# time-decoders.net
KiCad netlist of a schematic drawn in EAGLE
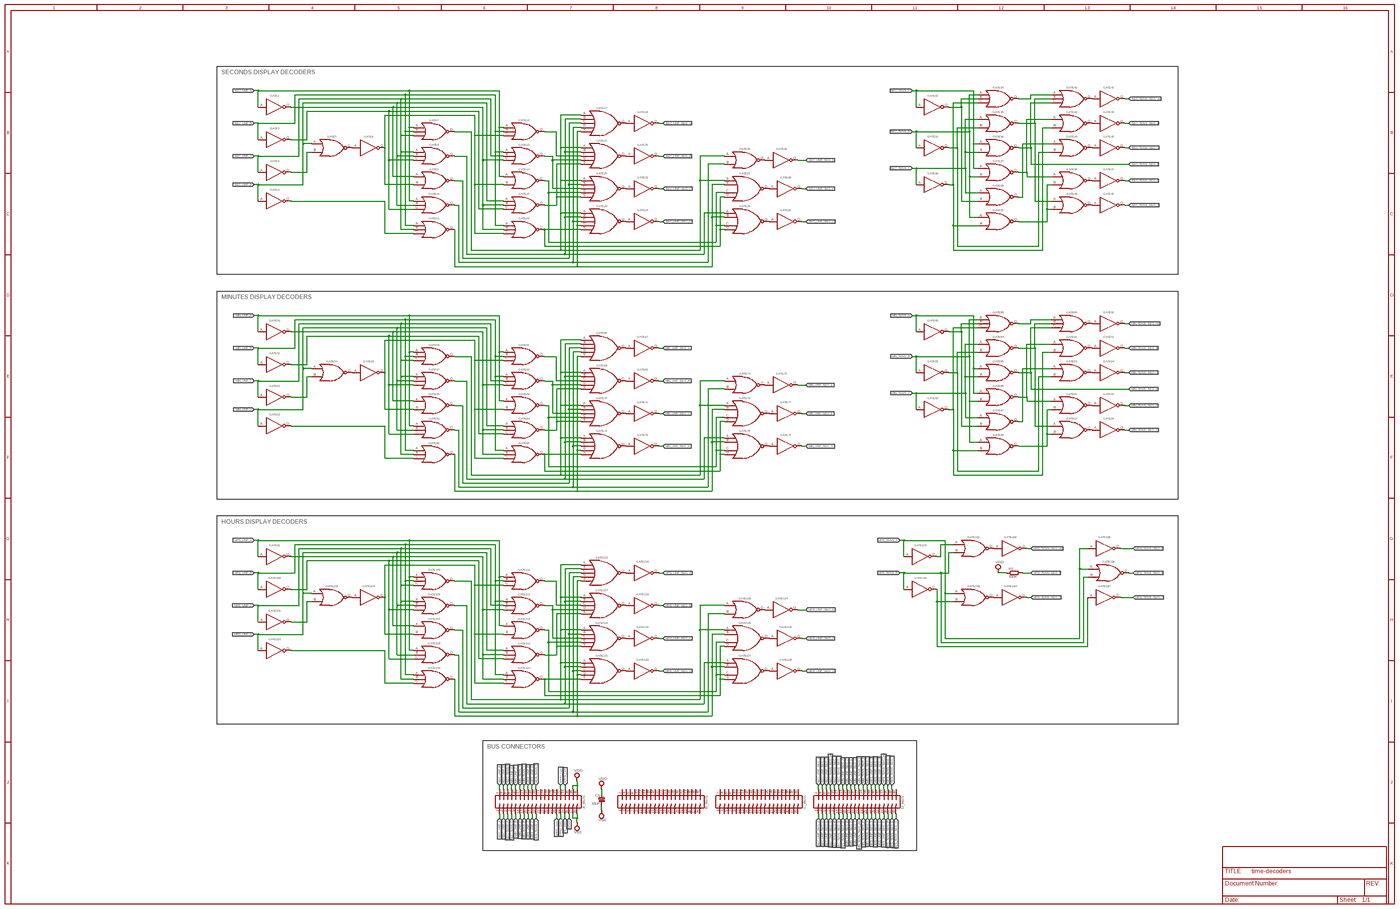
[diagram p0: schematic, sheet 1, overview]
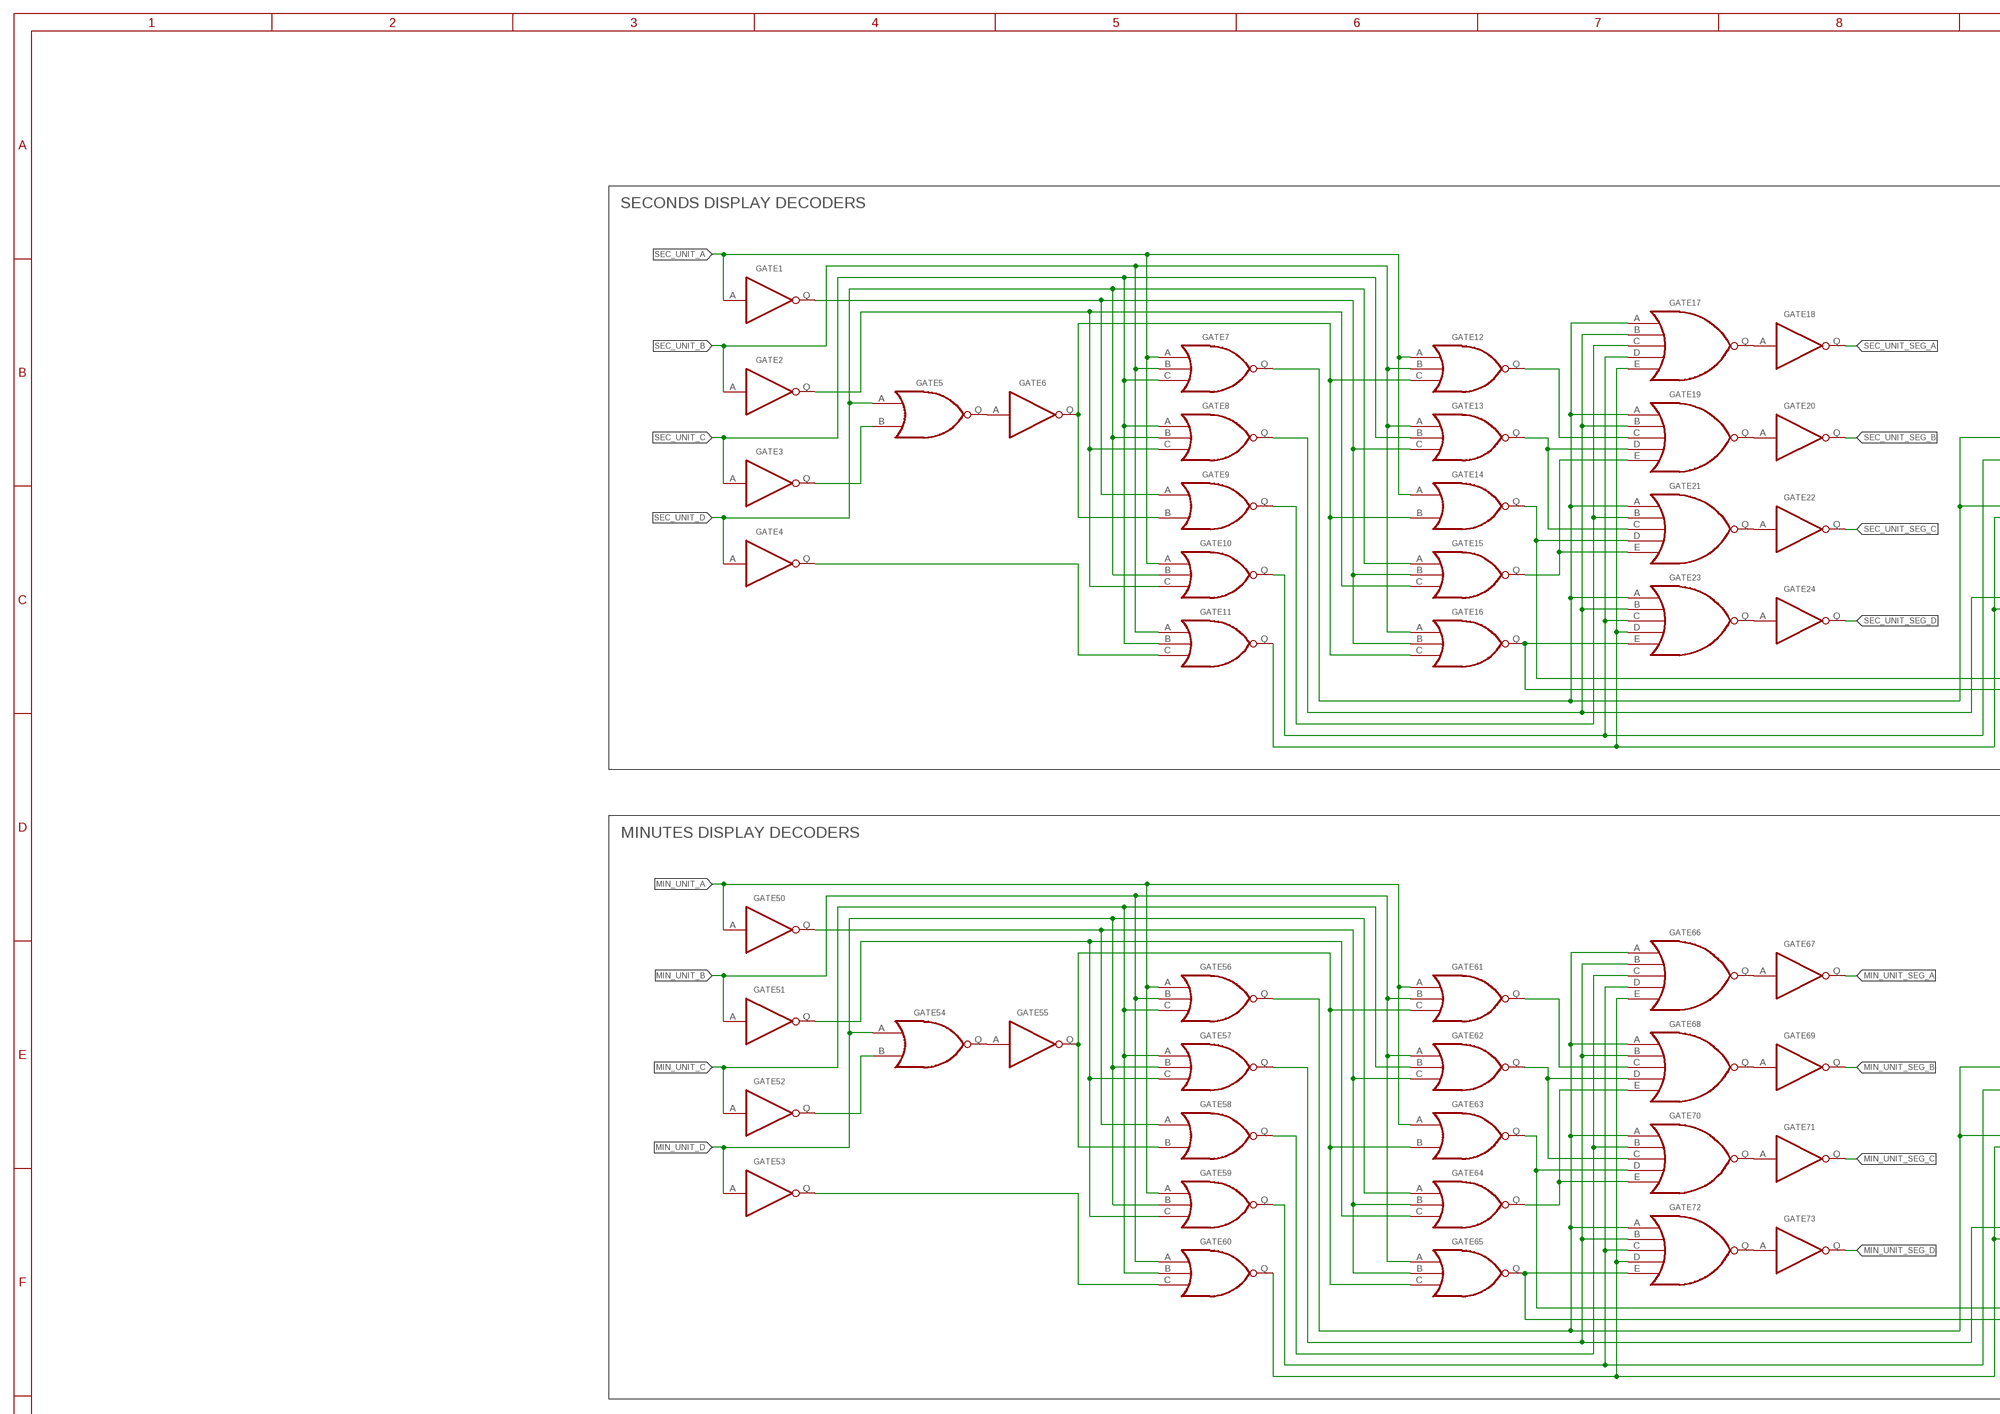
[diagram p1: schematic, sheet 1, part 1 of 4]
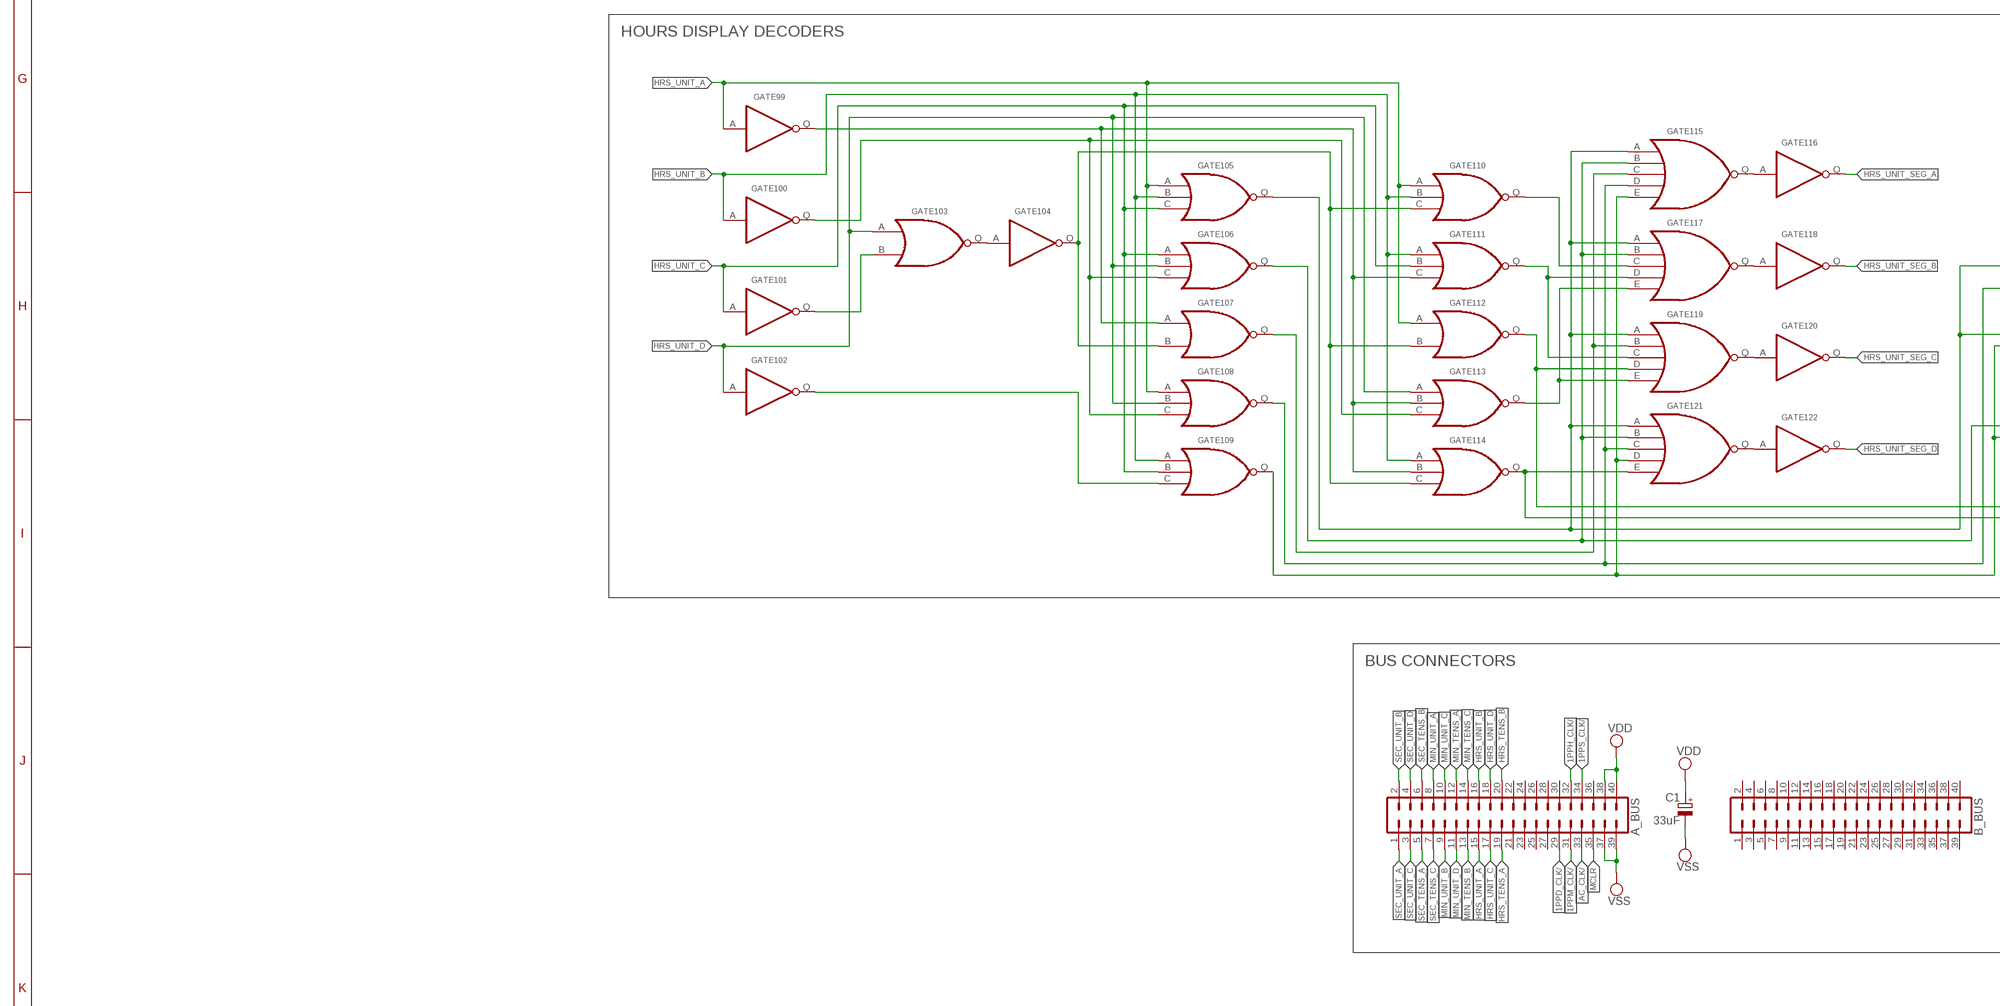
[diagram p2: schematic, sheet 1, part 2 of 4]
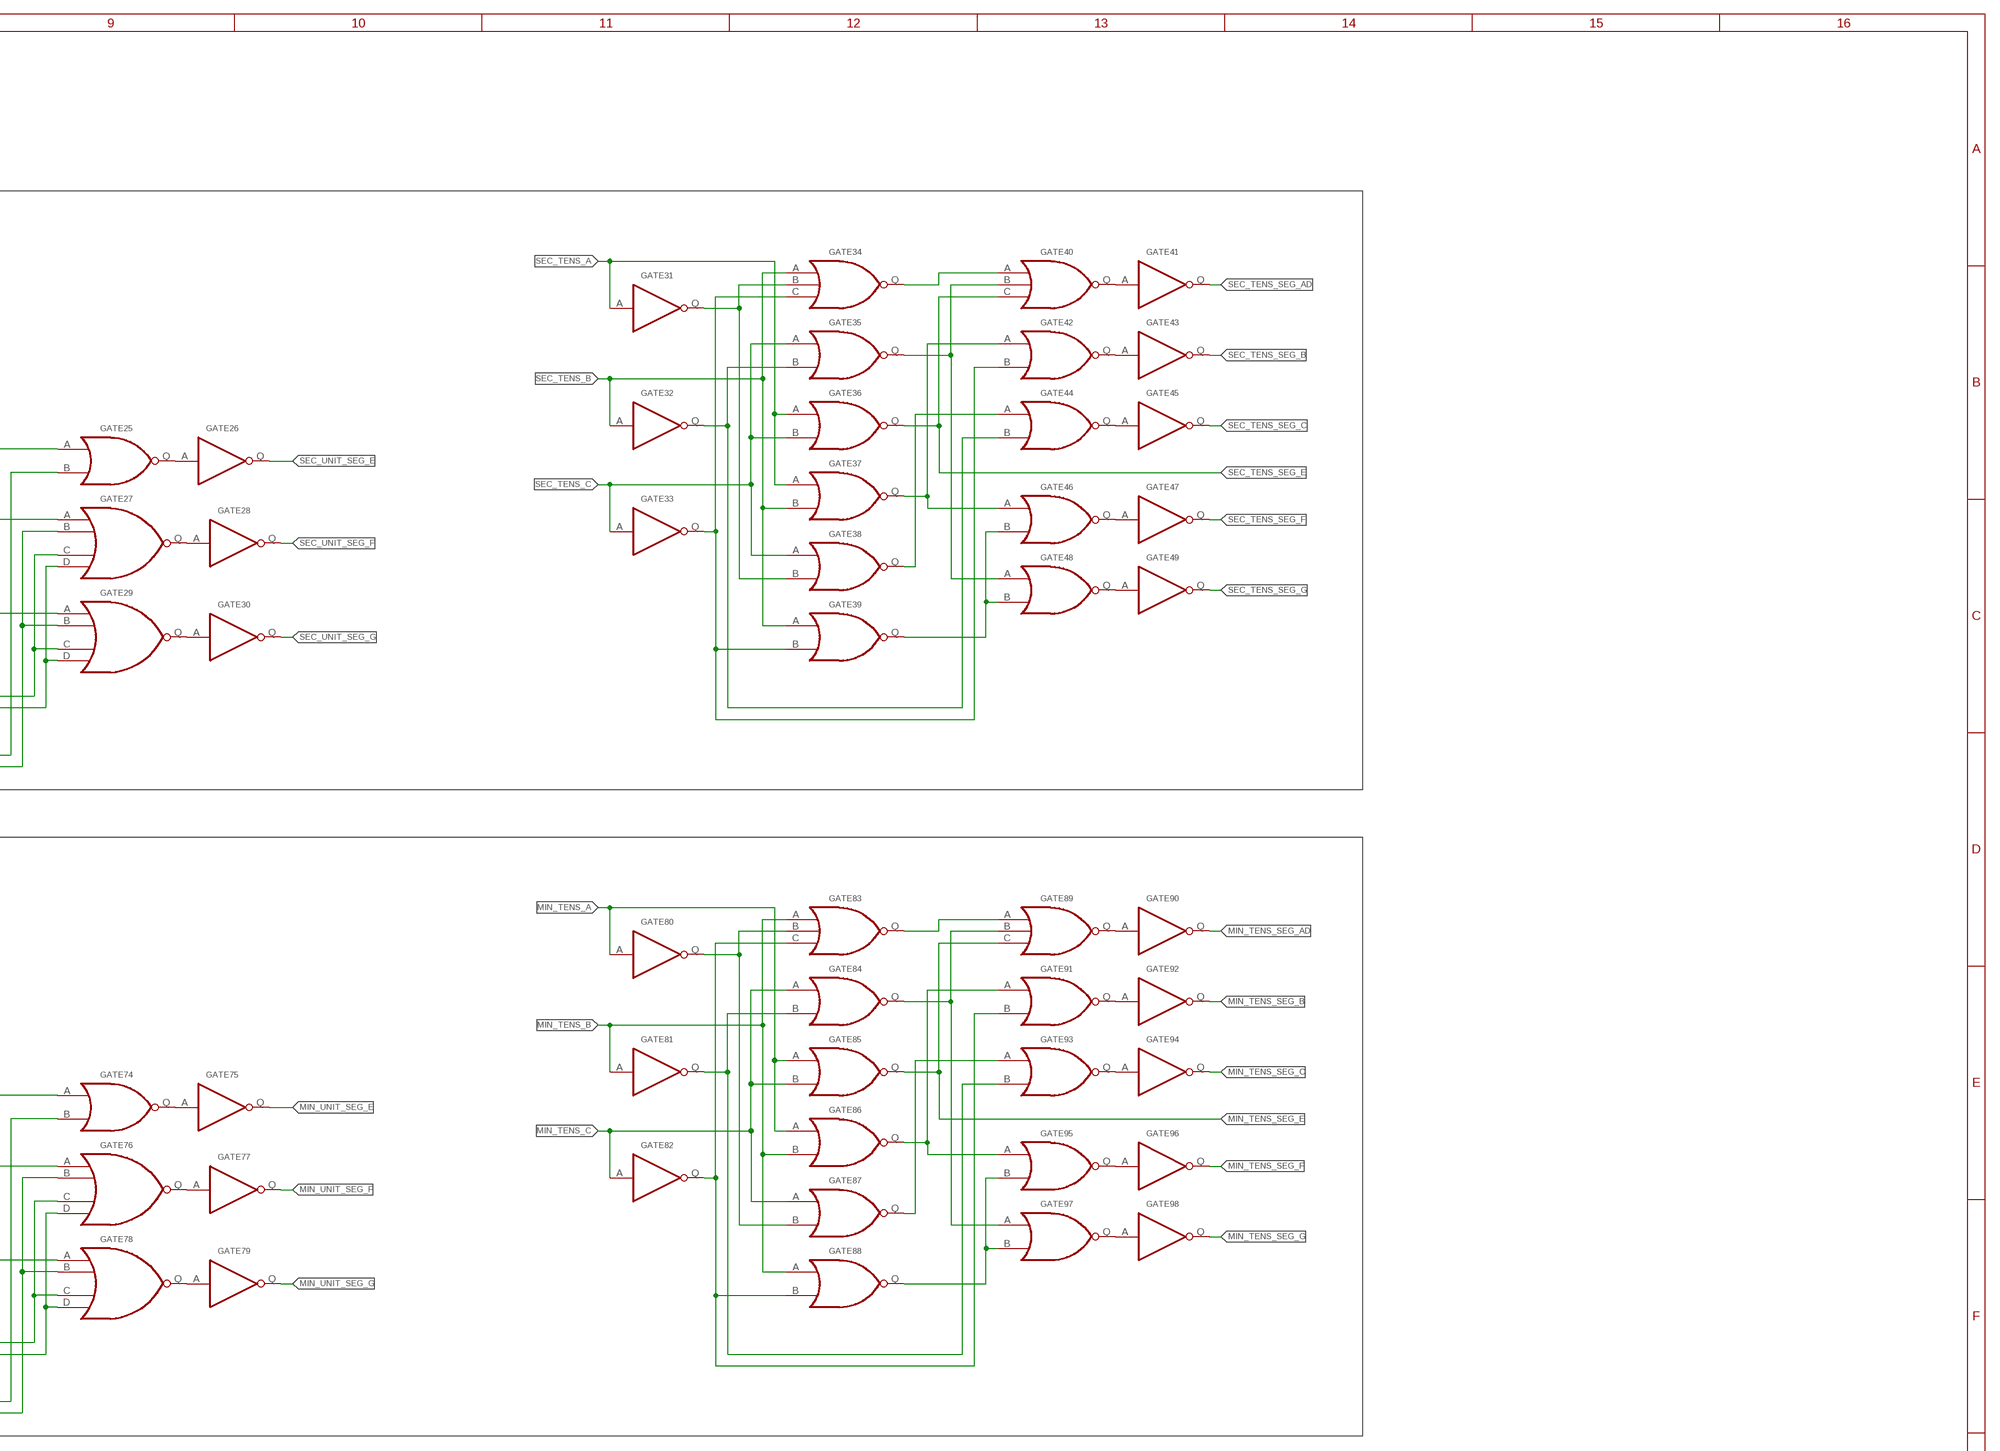
[diagram p3: schematic, sheet 1, part 3 of 4]
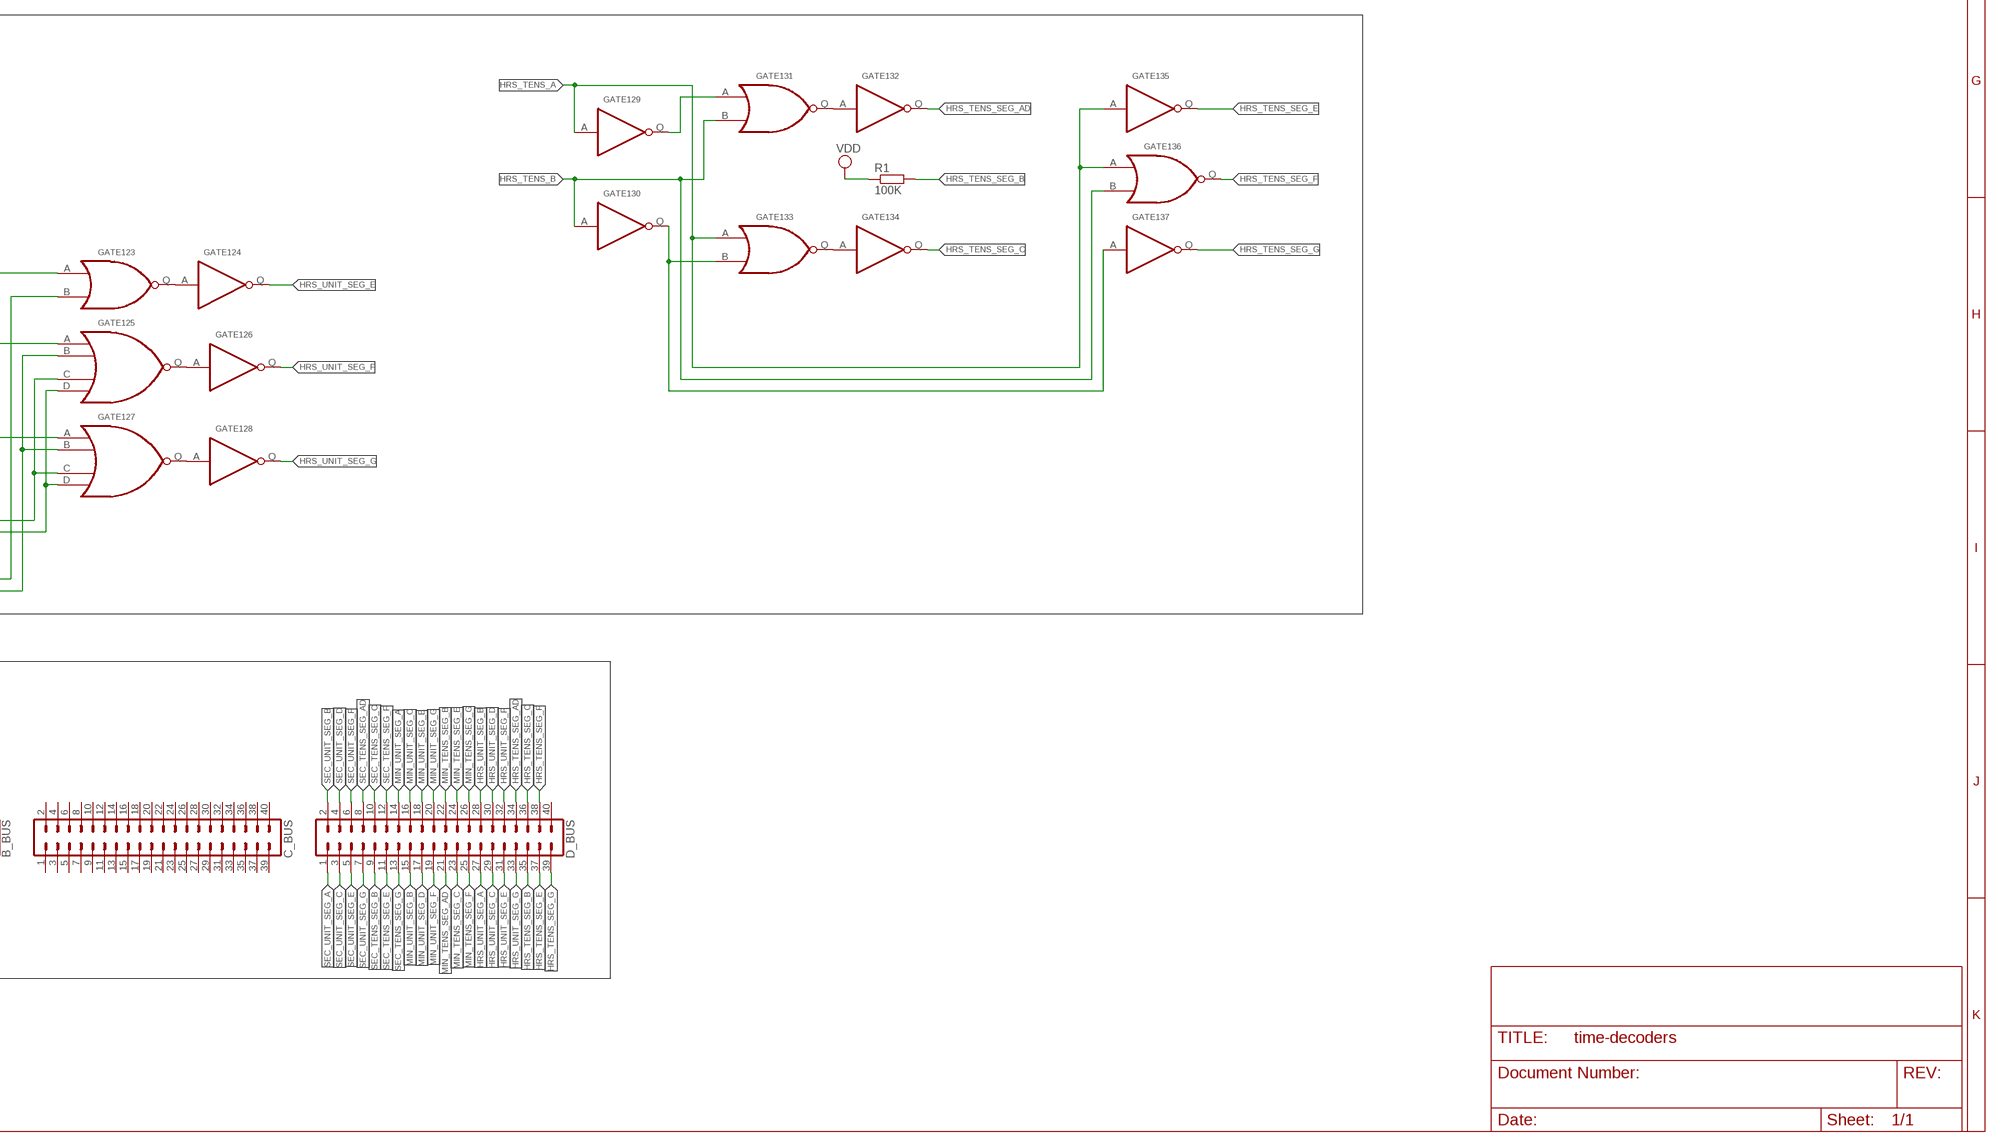
[diagram p4: schematic, sheet 1, part 4 of 4]

(export (version "E")
  (design (tool "Eeschema 10.0.6"))
  (components
    (comp (ref "A_BUS")
      (value "MA20-2")
      (footprint "eagle-import:MA20-2")
      (libsource (lib "eagle-import") (part "MA20-2"))
    )
    (comp (ref "B_BUS")
      (value "MA20-2")
      (footprint "eagle-import:MA20-2")
      (libsource (lib "eagle-import") (part "MA20-2"))
    )
    (comp (ref "C1")
      (value "33uF")
      (footprint "eagle-import:E2,5-6")
      (libsource (lib "eagle-import") (part "CPOL-EUE2.5-6"))
    )
    (comp (ref "C_BUS")
      (value "MA20-2")
      (footprint "eagle-import:MA20-2")
      (libsource (lib "eagle-import") (part "MA20-2"))
    )
    (comp (ref "D_BUS")
      (value "MA20-2")
      (footprint "eagle-import:MA20-2")
      (libsource (lib "eagle-import") (part "MA20-2"))
    )
    (comp (ref "GATE1")
      (value "INVERTER")
      (footprint "eagle-import:INVERTER")
      (libsource (lib "eagle-import") (part "INVERTER"))
    )
    (comp (ref "GATE2")
      (value "INVERTER")
      (footprint "eagle-import:INVERTER")
      (libsource (lib "eagle-import") (part "INVERTER"))
    )
    (comp (ref "GATE3")
      (value "INVERTER")
      (footprint "eagle-import:INVERTER")
      (libsource (lib "eagle-import") (part "INVERTER"))
    )
    (comp (ref "GATE4")
      (value "INVERTER")
      (footprint "eagle-import:INVERTER")
      (libsource (lib "eagle-import") (part "INVERTER"))
    )
    (comp (ref "GATE5")
      (value "2NOR")
      (footprint "eagle-import:2NOR")
      (libsource (lib "eagle-import") (part "2NOR"))
    )
    (comp (ref "GATE6")
      (value "INVERTER")
      (footprint "eagle-import:INVERTER")
      (libsource (lib "eagle-import") (part "INVERTER"))
    )
    (comp (ref "GATE7")
      (value "3NOR")
      (footprint "eagle-import:3NOR")
      (libsource (lib "eagle-import") (part "3NOR"))
    )
    (comp (ref "GATE8")
      (value "3NOR")
      (footprint "eagle-import:3NOR")
      (libsource (lib "eagle-import") (part "3NOR"))
    )
    (comp (ref "GATE9")
      (value "2NOR")
      (footprint "eagle-import:2NOR")
      (libsource (lib "eagle-import") (part "2NOR"))
    )
    (comp (ref "GATE10")
      (value "3NOR")
      (footprint "eagle-import:3NOR")
      (libsource (lib "eagle-import") (part "3NOR"))
    )
    (comp (ref "GATE11")
      (value "3NOR")
      (footprint "eagle-import:3NOR")
      (libsource (lib "eagle-import") (part "3NOR"))
    )
    (comp (ref "GATE12")
      (value "3NOR")
      (footprint "eagle-import:3NOR")
      (libsource (lib "eagle-import") (part "3NOR"))
    )
    (comp (ref "GATE13")
      (value "3NOR")
      (footprint "eagle-import:3NOR")
      (libsource (lib "eagle-import") (part "3NOR"))
    )
    (comp (ref "GATE14")
      (value "2NOR")
      (footprint "eagle-import:2NOR")
      (libsource (lib "eagle-import") (part "2NOR"))
    )
    (comp (ref "GATE15")
      (value "3NOR")
      (footprint "eagle-import:3NOR")
      (libsource (lib "eagle-import") (part "3NOR"))
    )
    (comp (ref "GATE16")
      (value "3NOR")
      (footprint "eagle-import:3NOR")
      (libsource (lib "eagle-import") (part "3NOR"))
    )
    (comp (ref "GATE17")
      (value "5NOR")
      (footprint "eagle-import:5NOR")
      (libsource (lib "eagle-import") (part "5NOR"))
    )
    (comp (ref "GATE18")
      (value "INVERTER")
      (footprint "eagle-import:INVERTER")
      (libsource (lib "eagle-import") (part "INVERTER"))
    )
    (comp (ref "GATE19")
      (value "5NOR")
      (footprint "eagle-import:5NOR")
      (libsource (lib "eagle-import") (part "5NOR"))
    )
    (comp (ref "GATE20")
      (value "INVERTER")
      (footprint "eagle-import:INVERTER")
      (libsource (lib "eagle-import") (part "INVERTER"))
    )
    (comp (ref "GATE21")
      (value "5NOR")
      (footprint "eagle-import:5NOR")
      (libsource (lib "eagle-import") (part "5NOR"))
    )
    (comp (ref "GATE22")
      (value "INVERTER")
      (footprint "eagle-import:INVERTER")
      (libsource (lib "eagle-import") (part "INVERTER"))
    )
    (comp (ref "GATE23")
      (value "5NOR")
      (footprint "eagle-import:5NOR")
      (libsource (lib "eagle-import") (part "5NOR"))
    )
    (comp (ref "GATE24")
      (value "INVERTER")
      (footprint "eagle-import:INVERTER")
      (libsource (lib "eagle-import") (part "INVERTER"))
    )
    (comp (ref "GATE25")
      (value "2NOR")
      (footprint "eagle-import:2NOR")
      (libsource (lib "eagle-import") (part "2NOR"))
    )
    (comp (ref "GATE26")
      (value "INVERTER")
      (footprint "eagle-import:INVERTER")
      (libsource (lib "eagle-import") (part "INVERTER"))
    )
    (comp (ref "GATE27")
      (value "4NOR")
      (footprint "eagle-import:4NOR")
      (libsource (lib "eagle-import") (part "4NOR"))
    )
    (comp (ref "GATE28")
      (value "INVERTER")
      (footprint "eagle-import:INVERTER")
      (libsource (lib "eagle-import") (part "INVERTER"))
    )
    (comp (ref "GATE29")
      (value "4NOR")
      (footprint "eagle-import:4NOR")
      (libsource (lib "eagle-import") (part "4NOR"))
    )
    (comp (ref "GATE30")
      (value "INVERTER")
      (footprint "eagle-import:INVERTER")
      (libsource (lib "eagle-import") (part "INVERTER"))
    )
    (comp (ref "GATE31")
      (value "INVERTER")
      (footprint "eagle-import:INVERTER")
      (libsource (lib "eagle-import") (part "INVERTER"))
    )
    (comp (ref "GATE32")
      (value "INVERTER")
      (footprint "eagle-import:INVERTER")
      (libsource (lib "eagle-import") (part "INVERTER"))
    )
    (comp (ref "GATE33")
      (value "INVERTER")
      (footprint "eagle-import:INVERTER")
      (libsource (lib "eagle-import") (part "INVERTER"))
    )
    (comp (ref "GATE34")
      (value "3NOR")
      (footprint "eagle-import:3NOR")
      (libsource (lib "eagle-import") (part "3NOR"))
    )
    (comp (ref "GATE35")
      (value "2NOR")
      (footprint "eagle-import:2NOR")
      (libsource (lib "eagle-import") (part "2NOR"))
    )
    (comp (ref "GATE36")
      (value "2NOR")
      (footprint "eagle-import:2NOR")
      (libsource (lib "eagle-import") (part "2NOR"))
    )
    (comp (ref "GATE37")
      (value "2NOR")
      (footprint "eagle-import:2NOR")
      (libsource (lib "eagle-import") (part "2NOR"))
    )
    (comp (ref "GATE38")
      (value "2NOR")
      (footprint "eagle-import:2NOR")
      (libsource (lib "eagle-import") (part "2NOR"))
    )
    (comp (ref "GATE39")
      (value "2NOR")
      (footprint "eagle-import:2NOR")
      (libsource (lib "eagle-import") (part "2NOR"))
    )
    (comp (ref "GATE40")
      (value "3NOR")
      (footprint "eagle-import:3NOR")
      (libsource (lib "eagle-import") (part "3NOR"))
    )
    (comp (ref "GATE41")
      (value "INVERTER")
      (footprint "eagle-import:INVERTER")
      (libsource (lib "eagle-import") (part "INVERTER"))
    )
    (comp (ref "GATE42")
      (value "2NOR")
      (footprint "eagle-import:2NOR")
      (libsource (lib "eagle-import") (part "2NOR"))
    )
    (comp (ref "GATE43")
      (value "INVERTER")
      (footprint "eagle-import:INVERTER")
      (libsource (lib "eagle-import") (part "INVERTER"))
    )
    (comp (ref "GATE44")
      (value "2NOR")
      (footprint "eagle-import:2NOR")
      (libsource (lib "eagle-import") (part "2NOR"))
    )
    (comp (ref "GATE45")
      (value "INVERTER")
      (footprint "eagle-import:INVERTER")
      (libsource (lib "eagle-import") (part "INVERTER"))
    )
    (comp (ref "GATE46")
      (value "2NOR")
      (footprint "eagle-import:2NOR")
      (libsource (lib "eagle-import") (part "2NOR"))
    )
    (comp (ref "GATE47")
      (value "INVERTER")
      (footprint "eagle-import:INVERTER")
      (libsource (lib "eagle-import") (part "INVERTER"))
    )
    (comp (ref "GATE48")
      (value "2NOR")
      (footprint "eagle-import:2NOR")
      (libsource (lib "eagle-import") (part "2NOR"))
    )
    (comp (ref "GATE49")
      (value "INVERTER")
      (footprint "eagle-import:INVERTER")
      (libsource (lib "eagle-import") (part "INVERTER"))
    )
    (comp (ref "GATE50")
      (value "INVERTER")
      (footprint "eagle-import:INVERTER")
      (libsource (lib "eagle-import") (part "INVERTER"))
    )
    (comp (ref "GATE51")
      (value "INVERTER")
      (footprint "eagle-import:INVERTER")
      (libsource (lib "eagle-import") (part "INVERTER"))
    )
    (comp (ref "GATE52")
      (value "INVERTER")
      (footprint "eagle-import:INVERTER")
      (libsource (lib "eagle-import") (part "INVERTER"))
    )
    (comp (ref "GATE53")
      (value "INVERTER")
      (footprint "eagle-import:INVERTER")
      (libsource (lib "eagle-import") (part "INVERTER"))
    )
    (comp (ref "GATE54")
      (value "2NOR")
      (footprint "eagle-import:2NOR")
      (libsource (lib "eagle-import") (part "2NOR"))
    )
    (comp (ref "GATE55")
      (value "INVERTER")
      (footprint "eagle-import:INVERTER")
      (libsource (lib "eagle-import") (part "INVERTER"))
    )
    (comp (ref "GATE56")
      (value "3NOR")
      (footprint "eagle-import:3NOR")
      (libsource (lib "eagle-import") (part "3NOR"))
    )
    (comp (ref "GATE57")
      (value "3NOR")
      (footprint "eagle-import:3NOR")
      (libsource (lib "eagle-import") (part "3NOR"))
    )
    (comp (ref "GATE58")
      (value "2NOR")
      (footprint "eagle-import:2NOR")
      (libsource (lib "eagle-import") (part "2NOR"))
    )
    (comp (ref "GATE59")
      (value "3NOR")
      (footprint "eagle-import:3NOR")
      (libsource (lib "eagle-import") (part "3NOR"))
    )
    (comp (ref "GATE60")
      (value "3NOR")
      (footprint "eagle-import:3NOR")
      (libsource (lib "eagle-import") (part "3NOR"))
    )
    (comp (ref "GATE61")
      (value "3NOR")
      (footprint "eagle-import:3NOR")
      (libsource (lib "eagle-import") (part "3NOR"))
    )
    (comp (ref "GATE62")
      (value "3NOR")
      (footprint "eagle-import:3NOR")
      (libsource (lib "eagle-import") (part "3NOR"))
    )
    (comp (ref "GATE63")
      (value "2NOR")
      (footprint "eagle-import:2NOR")
      (libsource (lib "eagle-import") (part "2NOR"))
    )
    (comp (ref "GATE64")
      (value "3NOR")
      (footprint "eagle-import:3NOR")
      (libsource (lib "eagle-import") (part "3NOR"))
    )
    (comp (ref "GATE65")
      (value "3NOR")
      (footprint "eagle-import:3NOR")
      (libsource (lib "eagle-import") (part "3NOR"))
    )
    (comp (ref "GATE66")
      (value "5NOR")
      (footprint "eagle-import:5NOR")
      (libsource (lib "eagle-import") (part "5NOR"))
    )
    (comp (ref "GATE67")
      (value "INVERTER")
      (footprint "eagle-import:INVERTER")
      (libsource (lib "eagle-import") (part "INVERTER"))
    )
    (comp (ref "GATE68")
      (value "5NOR")
      (footprint "eagle-import:5NOR")
      (libsource (lib "eagle-import") (part "5NOR"))
    )
    (comp (ref "GATE69")
      (value "INVERTER")
      (footprint "eagle-import:INVERTER")
      (libsource (lib "eagle-import") (part "INVERTER"))
    )
    (comp (ref "GATE70")
      (value "5NOR")
      (footprint "eagle-import:5NOR")
      (libsource (lib "eagle-import") (part "5NOR"))
    )
    (comp (ref "GATE71")
      (value "INVERTER")
      (footprint "eagle-import:INVERTER")
      (libsource (lib "eagle-import") (part "INVERTER"))
    )
    (comp (ref "GATE72")
      (value "5NOR")
      (footprint "eagle-import:5NOR")
      (libsource (lib "eagle-import") (part "5NOR"))
    )
    (comp (ref "GATE73")
      (value "INVERTER")
      (footprint "eagle-import:INVERTER")
      (libsource (lib "eagle-import") (part "INVERTER"))
    )
    (comp (ref "GATE74")
      (value "2NOR")
      (footprint "eagle-import:2NOR")
      (libsource (lib "eagle-import") (part "2NOR"))
    )
    (comp (ref "GATE75")
      (value "INVERTER")
      (footprint "eagle-import:INVERTER")
      (libsource (lib "eagle-import") (part "INVERTER"))
    )
    (comp (ref "GATE76")
      (value "4NOR")
      (footprint "eagle-import:4NOR")
      (libsource (lib "eagle-import") (part "4NOR"))
    )
    (comp (ref "GATE77")
      (value "INVERTER")
      (footprint "eagle-import:INVERTER")
      (libsource (lib "eagle-import") (part "INVERTER"))
    )
    (comp (ref "GATE78")
      (value "4NOR")
      (footprint "eagle-import:4NOR")
      (libsource (lib "eagle-import") (part "4NOR"))
    )
    (comp (ref "GATE79")
      (value "INVERTER")
      (footprint "eagle-import:INVERTER")
      (libsource (lib "eagle-import") (part "INVERTER"))
    )
    (comp (ref "GATE80")
      (value "INVERTER")
      (footprint "eagle-import:INVERTER")
      (libsource (lib "eagle-import") (part "INVERTER"))
    )
    (comp (ref "GATE81")
      (value "INVERTER")
      (footprint "eagle-import:INVERTER")
      (libsource (lib "eagle-import") (part "INVERTER"))
    )
    (comp (ref "GATE82")
      (value "INVERTER")
      (footprint "eagle-import:INVERTER")
      (libsource (lib "eagle-import") (part "INVERTER"))
    )
    (comp (ref "GATE83")
      (value "3NOR")
      (footprint "eagle-import:3NOR")
      (libsource (lib "eagle-import") (part "3NOR"))
    )
    (comp (ref "GATE84")
      (value "2NOR")
      (footprint "eagle-import:2NOR")
      (libsource (lib "eagle-import") (part "2NOR"))
    )
    (comp (ref "GATE85")
      (value "2NOR")
      (footprint "eagle-import:2NOR")
      (libsource (lib "eagle-import") (part "2NOR"))
    )
    (comp (ref "GATE86")
      (value "2NOR")
      (footprint "eagle-import:2NOR")
      (libsource (lib "eagle-import") (part "2NOR"))
    )
    (comp (ref "GATE87")
      (value "2NOR")
      (footprint "eagle-import:2NOR")
      (libsource (lib "eagle-import") (part "2NOR"))
    )
    (comp (ref "GATE88")
      (value "2NOR")
      (footprint "eagle-import:2NOR")
      (libsource (lib "eagle-import") (part "2NOR"))
    )
    (comp (ref "GATE89")
      (value "3NOR")
      (footprint "eagle-import:3NOR")
      (libsource (lib "eagle-import") (part "3NOR"))
    )
    (comp (ref "GATE90")
      (value "INVERTER")
      (footprint "eagle-import:INVERTER")
      (libsource (lib "eagle-import") (part "INVERTER"))
    )
    (comp (ref "GATE91")
      (value "2NOR")
      (footprint "eagle-import:2NOR")
      (libsource (lib "eagle-import") (part "2NOR"))
    )
    (comp (ref "GATE92")
      (value "INVERTER")
      (footprint "eagle-import:INVERTER")
      (libsource (lib "eagle-import") (part "INVERTER"))
    )
    (comp (ref "GATE93")
      (value "2NOR")
      (footprint "eagle-import:2NOR")
      (libsource (lib "eagle-import") (part "2NOR"))
    )
    (comp (ref "GATE94")
      (value "INVERTER")
      (footprint "eagle-import:INVERTER")
      (libsource (lib "eagle-import") (part "INVERTER"))
    )
    (comp (ref "GATE95")
      (value "2NOR")
      (footprint "eagle-import:2NOR")
      (libsource (lib "eagle-import") (part "2NOR"))
    )
    (comp (ref "GATE96")
      (value "INVERTER")
      (footprint "eagle-import:INVERTER")
      (libsource (lib "eagle-import") (part "INVERTER"))
    )
    (comp (ref "GATE97")
      (value "2NOR")
      (footprint "eagle-import:2NOR")
      (libsource (lib "eagle-import") (part "2NOR"))
    )
    (comp (ref "GATE98")
      (value "INVERTER")
      (footprint "eagle-import:INVERTER")
      (libsource (lib "eagle-import") (part "INVERTER"))
    )
    (comp (ref "GATE99")
      (value "INVERTER")
      (footprint "eagle-import:INVERTER")
      (libsource (lib "eagle-import") (part "INVERTER"))
    )
    (comp (ref "GATE100")
      (value "INVERTER")
      (footprint "eagle-import:INVERTER")
      (libsource (lib "eagle-import") (part "INVERTER"))
    )
    (comp (ref "GATE101")
      (value "INVERTER")
      (footprint "eagle-import:INVERTER")
      (libsource (lib "eagle-import") (part "INVERTER"))
    )
    (comp (ref "GATE102")
      (value "INVERTER")
      (footprint "eagle-import:INVERTER")
      (libsource (lib "eagle-import") (part "INVERTER"))
    )
    (comp (ref "GATE103")
      (value "2NOR")
      (footprint "eagle-import:2NOR")
      (libsource (lib "eagle-import") (part "2NOR"))
    )
    (comp (ref "GATE104")
      (value "INVERTER")
      (footprint "eagle-import:INVERTER")
      (libsource (lib "eagle-import") (part "INVERTER"))
    )
    (comp (ref "GATE105")
      (value "3NOR")
      (footprint "eagle-import:3NOR")
      (libsource (lib "eagle-import") (part "3NOR"))
    )
    (comp (ref "GATE106")
      (value "3NOR")
      (footprint "eagle-import:3NOR")
      (libsource (lib "eagle-import") (part "3NOR"))
    )
    (comp (ref "GATE107")
      (value "2NOR")
      (footprint "eagle-import:2NOR")
      (libsource (lib "eagle-import") (part "2NOR"))
    )
    (comp (ref "GATE108")
      (value "3NOR")
      (footprint "eagle-import:3NOR")
      (libsource (lib "eagle-import") (part "3NOR"))
    )
    (comp (ref "GATE109")
      (value "3NOR")
      (footprint "eagle-import:3NOR")
      (libsource (lib "eagle-import") (part "3NOR"))
    )
    (comp (ref "GATE110")
      (value "3NOR")
      (footprint "eagle-import:3NOR")
      (libsource (lib "eagle-import") (part "3NOR"))
    )
    (comp (ref "GATE111")
      (value "3NOR")
      (footprint "eagle-import:3NOR")
      (libsource (lib "eagle-import") (part "3NOR"))
    )
    (comp (ref "GATE112")
      (value "2NOR")
      (footprint "eagle-import:2NOR")
      (libsource (lib "eagle-import") (part "2NOR"))
    )
    (comp (ref "GATE113")
      (value "3NOR")
      (footprint "eagle-import:3NOR")
      (libsource (lib "eagle-import") (part "3NOR"))
    )
    (comp (ref "GATE114")
      (value "3NOR")
      (footprint "eagle-import:3NOR")
      (libsource (lib "eagle-import") (part "3NOR"))
    )
    (comp (ref "GATE115")
      (value "5NOR")
      (footprint "eagle-import:5NOR")
      (libsource (lib "eagle-import") (part "5NOR"))
    )
    (comp (ref "GATE116")
      (value "INVERTER")
      (footprint "eagle-import:INVERTER")
      (libsource (lib "eagle-import") (part "INVERTER"))
    )
    (comp (ref "GATE117")
      (value "5NOR")
      (footprint "eagle-import:5NOR")
      (libsource (lib "eagle-import") (part "5NOR"))
    )
    (comp (ref "GATE118")
      (value "INVERTER")
      (footprint "eagle-import:INVERTER")
      (libsource (lib "eagle-import") (part "INVERTER"))
    )
    (comp (ref "GATE119")
      (value "5NOR")
      (footprint "eagle-import:5NOR")
      (libsource (lib "eagle-import") (part "5NOR"))
    )
    (comp (ref "GATE120")
      (value "INVERTER")
      (footprint "eagle-import:INVERTER")
      (libsource (lib "eagle-import") (part "INVERTER"))
    )
    (comp (ref "GATE121")
      (value "5NOR")
      (footprint "eagle-import:5NOR")
      (libsource (lib "eagle-import") (part "5NOR"))
    )
    (comp (ref "GATE122")
      (value "INVERTER")
      (footprint "eagle-import:INVERTER")
      (libsource (lib "eagle-import") (part "INVERTER"))
    )
    (comp (ref "GATE123")
      (value "2NOR")
      (footprint "eagle-import:2NOR")
      (libsource (lib "eagle-import") (part "2NOR"))
    )
    (comp (ref "GATE124")
      (value "INVERTER")
      (footprint "eagle-import:INVERTER")
      (libsource (lib "eagle-import") (part "INVERTER"))
    )
    (comp (ref "GATE125")
      (value "4NOR")
      (footprint "eagle-import:4NOR")
      (libsource (lib "eagle-import") (part "4NOR"))
    )
    (comp (ref "GATE126")
      (value "INVERTER")
      (footprint "eagle-import:INVERTER")
      (libsource (lib "eagle-import") (part "INVERTER"))
    )
    (comp (ref "GATE127")
      (value "4NOR")
      (footprint "eagle-import:4NOR")
      (libsource (lib "eagle-import") (part "4NOR"))
    )
    (comp (ref "GATE128")
      (value "INVERTER")
      (footprint "eagle-import:INVERTER")
      (libsource (lib "eagle-import") (part "INVERTER"))
    )
    (comp (ref "GATE129")
      (value "INVERTER")
      (footprint "eagle-import:INVERTER")
      (libsource (lib "eagle-import") (part "INVERTER"))
    )
    (comp (ref "GATE130")
      (value "INVERTER")
      (footprint "eagle-import:INVERTER")
      (libsource (lib "eagle-import") (part "INVERTER"))
    )
    (comp (ref "GATE131")
      (value "2NOR")
      (footprint "eagle-import:2NOR")
      (libsource (lib "eagle-import") (part "2NOR"))
    )
    (comp (ref "GATE132")
      (value "INVERTER")
      (footprint "eagle-import:INVERTER")
      (libsource (lib "eagle-import") (part "INVERTER"))
    )
    (comp (ref "GATE133")
      (value "2NOR")
      (footprint "eagle-import:2NOR")
      (libsource (lib "eagle-import") (part "2NOR"))
    )
    (comp (ref "GATE134")
      (value "INVERTER")
      (footprint "eagle-import:INVERTER")
      (libsource (lib "eagle-import") (part "INVERTER"))
    )
    (comp (ref "GATE135")
      (value "INVERTER")
      (footprint "eagle-import:INVERTER")
      (libsource (lib "eagle-import") (part "INVERTER"))
    )
    (comp (ref "GATE136")
      (value "2NOR")
      (footprint "eagle-import:2NOR")
      (libsource (lib "eagle-import") (part "2NOR"))
    )
    (comp (ref "GATE137")
      (value "INVERTER")
      (footprint "eagle-import:INVERTER")
      (libsource (lib "eagle-import") (part "INVERTER"))
    )
    (comp (ref "R1")
      (value "100K")
      (footprint "eagle-import:0207_2V")
      (libsource (lib "eagle-import") (part "R-EU_0207/2V"))
    )
  )
  (nets
    (net (code "1") (name "1PPD_CLK{slash}") (class "Default")
      (node (ref "A_BUS") (pin "29") (pinfunction "29_29") (pintype "passive"))
    )
    (net (code "2") (name "1PPH_CLK{slash}") (class "Default")
      (node (ref "A_BUS") (pin "32") (pinfunction "32_32") (pintype "passive"))
    )
    (net (code "3") (name "1PPM_CLK{slash}") (class "Default")
      (node (ref "A_BUS") (pin "31") (pinfunction "31_31") (pintype "passive"))
    )
    (net (code "4") (name "1PPS_CLK{slash}") (class "Default")
      (node (ref "A_BUS") (pin "34") (pinfunction "34_34") (pintype "passive"))
    )
    (net (code "5") (name "AC_CLK{slash}") (class "Default")
      (node (ref "A_BUS") (pin "33") (pinfunction "33_33") (pintype "passive"))
    )
    (net (code "6") (name "HRS_TENS_A") (class "Default")
      (node (ref "A_BUS") (pin "19") (pinfunction "19_19") (pintype "passive"))
      (node (ref "GATE129") (pin "A") (pinfunction "A_A") (pintype "input"))
      (node (ref "GATE133") (pin "A") (pinfunction "A_A") (pintype "input"))
      (node (ref "GATE135") (pin "A") (pinfunction "A_A") (pintype "input"))
      (node (ref "GATE136") (pin "A") (pinfunction "A_A") (pintype "input"))
    )
    (net (code "7") (name "HRS_TENS_B") (class "Default")
      (node (ref "A_BUS") (pin "20") (pinfunction "20_20") (pintype "passive"))
      (node (ref "GATE130") (pin "A") (pinfunction "A_A") (pintype "input"))
      (node (ref "GATE131") (pin "B") (pinfunction "B_B") (pintype "input"))
      (node (ref "GATE136") (pin "B") (pinfunction "B_B") (pintype "input"))
    )
    (net (code "8") (name "HRS_TENS_SEG_AD") (class "Default")
      (node (ref "D_BUS") (pin "34") (pinfunction "34_34") (pintype "passive"))
      (node (ref "GATE132") (pin "Q") (pinfunction "Q_Q") (pintype "output"))
    )
    (net (code "9") (name "HRS_TENS_SEG_B") (class "Default")
      (node (ref "D_BUS") (pin "35") (pinfunction "35_35") (pintype "passive"))
      (node (ref "R1") (pin "2") (pinfunction "2_2") (pintype "passive"))
    )
    (net (code "10") (name "HRS_TENS_SEG_C") (class "Default")
      (node (ref "D_BUS") (pin "36") (pinfunction "36_36") (pintype "passive"))
      (node (ref "GATE134") (pin "Q") (pinfunction "Q_Q") (pintype "output"))
    )
    (net (code "11") (name "HRS_TENS_SEG_E") (class "Default")
      (node (ref "D_BUS") (pin "37") (pinfunction "37_37") (pintype "passive"))
      (node (ref "GATE135") (pin "Q") (pinfunction "Q_Q") (pintype "output"))
    )
    (net (code "12") (name "HRS_TENS_SEG_F") (class "Default")
      (node (ref "D_BUS") (pin "38") (pinfunction "38_38") (pintype "passive"))
      (node (ref "GATE136") (pin "Q") (pinfunction "Q_Q") (pintype "output"))
    )
    (net (code "13") (name "HRS_TENS_SEG_G") (class "Default")
      (node (ref "D_BUS") (pin "39") (pinfunction "39_39") (pintype "passive"))
      (node (ref "GATE137") (pin "Q") (pinfunction "Q_Q") (pintype "output"))
    )
    (net (code "14") (name "HRS_UNIT_A") (class "Default")
      (node (ref "A_BUS") (pin "15") (pinfunction "15_15") (pintype "passive"))
      (node (ref "GATE105") (pin "A") (pinfunction "A_A") (pintype "input"))
      (node (ref "GATE108") (pin "A") (pinfunction "A_A") (pintype "input"))
      (node (ref "GATE110") (pin "A") (pinfunction "A_A") (pintype "input"))
      (node (ref "GATE112") (pin "A") (pinfunction "A_A") (pintype "input"))
      (node (ref "GATE99") (pin "A") (pinfunction "A_A") (pintype "input"))
    )
    (net (code "15") (name "HRS_UNIT_B") (class "Default")
      (node (ref "A_BUS") (pin "16") (pinfunction "16_16") (pintype "passive"))
      (node (ref "GATE100") (pin "A") (pinfunction "A_A") (pintype "input"))
      (node (ref "GATE105") (pin "B") (pinfunction "B_B") (pintype "input"))
      (node (ref "GATE109") (pin "A") (pinfunction "A_A") (pintype "input"))
      (node (ref "GATE110") (pin "B") (pinfunction "B_B") (pintype "input"))
      (node (ref "GATE111") (pin "A") (pinfunction "A_A") (pintype "input"))
      (node (ref "GATE114") (pin "A") (pinfunction "A_A") (pintype "input"))
    )
    (net (code "16") (name "HRS_UNIT_C") (class "Default")
      (node (ref "A_BUS") (pin "17") (pinfunction "17_17") (pintype "passive"))
      (node (ref "GATE101") (pin "A") (pinfunction "A_A") (pintype "input"))
      (node (ref "GATE105") (pin "C") (pinfunction "C_C") (pintype "input"))
      (node (ref "GATE106") (pin "A") (pinfunction "A_A") (pintype "input"))
      (node (ref "GATE109") (pin "B") (pinfunction "B_B") (pintype "input"))
      (node (ref "GATE111") (pin "B") (pinfunction "B_B") (pintype "input"))
    )
    (net (code "17") (name "HRS_UNIT_D") (class "Default")
      (node (ref "A_BUS") (pin "18") (pinfunction "18_18") (pintype "passive"))
      (node (ref "GATE102") (pin "A") (pinfunction "A_A") (pintype "input"))
      (node (ref "GATE103") (pin "A") (pinfunction "A_A") (pintype "input"))
      (node (ref "GATE106") (pin "B") (pinfunction "B_B") (pintype "input"))
      (node (ref "GATE108") (pin "B") (pinfunction "B_B") (pintype "input"))
      (node (ref "GATE113") (pin "A") (pinfunction "A_A") (pintype "input"))
    )
    (net (code "18") (name "HRS_UNIT_SEG_A") (class "Default")
      (node (ref "D_BUS") (pin "27") (pinfunction "27_27") (pintype "passive"))
      (node (ref "GATE116") (pin "Q") (pinfunction "Q_Q") (pintype "output"))
    )
    (net (code "19") (name "HRS_UNIT_SEG_B") (class "Default")
      (node (ref "D_BUS") (pin "28") (pinfunction "28_28") (pintype "passive"))
      (node (ref "GATE118") (pin "Q") (pinfunction "Q_Q") (pintype "output"))
    )
    (net (code "20") (name "HRS_UNIT_SEG_C") (class "Default")
      (node (ref "D_BUS") (pin "29") (pinfunction "29_29") (pintype "passive"))
      (node (ref "GATE120") (pin "Q") (pinfunction "Q_Q") (pintype "output"))
    )
    (net (code "21") (name "HRS_UNIT_SEG_D") (class "Default")
      (node (ref "D_BUS") (pin "30") (pinfunction "30_30") (pintype "passive"))
      (node (ref "GATE122") (pin "Q") (pinfunction "Q_Q") (pintype "output"))
    )
    (net (code "22") (name "HRS_UNIT_SEG_E") (class "Default")
      (node (ref "D_BUS") (pin "31") (pinfunction "31_31") (pintype "passive"))
      (node (ref "GATE124") (pin "Q") (pinfunction "Q_Q") (pintype "output"))
    )
    (net (code "23") (name "HRS_UNIT_SEG_F") (class "Default")
      (node (ref "D_BUS") (pin "32") (pinfunction "32_32") (pintype "passive"))
      (node (ref "GATE126") (pin "Q") (pinfunction "Q_Q") (pintype "output"))
    )
    (net (code "24") (name "HRS_UNIT_SEG_G") (class "Default")
      (node (ref "D_BUS") (pin "33") (pinfunction "33_33") (pintype "passive"))
      (node (ref "GATE128") (pin "Q") (pinfunction "Q_Q") (pintype "output"))
    )
    (net (code "25") (name "MCLR") (class "Default")
      (node (ref "A_BUS") (pin "35") (pinfunction "35_35") (pintype "passive"))
    )
    (net (code "26") (name "MIN_TENS_A") (class "Default")
      (node (ref "A_BUS") (pin "12") (pinfunction "12_12") (pintype "passive"))
      (node (ref "GATE80") (pin "A") (pinfunction "A_A") (pintype "input"))
      (node (ref "GATE85") (pin "A") (pinfunction "A_A") (pintype "input"))
      (node (ref "GATE86") (pin "A") (pinfunction "A_A") (pintype "input"))
    )
    (net (code "27") (name "MIN_TENS_B") (class "Default")
      (node (ref "A_BUS") (pin "13") (pinfunction "13_13") (pintype "passive"))
      (node (ref "GATE81") (pin "A") (pinfunction "A_A") (pintype "input"))
      (node (ref "GATE83") (pin "A") (pinfunction "A_A") (pintype "input"))
      (node (ref "GATE86") (pin "B") (pinfunction "B_B") (pintype "input"))
      (node (ref "GATE88") (pin "A") (pinfunction "A_A") (pintype "input"))
    )
    (net (code "28") (name "MIN_TENS_C") (class "Default")
      (node (ref "A_BUS") (pin "14") (pinfunction "14_14") (pintype "passive"))
      (node (ref "GATE82") (pin "A") (pinfunction "A_A") (pintype "input"))
      (node (ref "GATE84") (pin "A") (pinfunction "A_A") (pintype "input"))
      (node (ref "GATE85") (pin "B") (pinfunction "B_B") (pintype "input"))
      (node (ref "GATE87") (pin "A") (pinfunction "A_A") (pintype "input"))
    )
    (net (code "29") (name "MIN_TENS_SEG_AD") (class "Default")
      (node (ref "D_BUS") (pin "21") (pinfunction "21_21") (pintype "passive"))
      (node (ref "GATE90") (pin "Q") (pinfunction "Q_Q") (pintype "output"))
    )
    (net (code "30") (name "MIN_TENS_SEG_B") (class "Default")
      (node (ref "D_BUS") (pin "22") (pinfunction "22_22") (pintype "passive"))
      (node (ref "GATE92") (pin "Q") (pinfunction "Q_Q") (pintype "output"))
    )
    (net (code "31") (name "MIN_TENS_SEG_C") (class "Default")
      (node (ref "D_BUS") (pin "23") (pinfunction "23_23") (pintype "passive"))
      (node (ref "GATE94") (pin "Q") (pinfunction "Q_Q") (pintype "output"))
    )
    (net (code "32") (name "MIN_TENS_SEG_E") (class "Default")
      (node (ref "D_BUS") (pin "24") (pinfunction "24_24") (pintype "passive"))
      (node (ref "GATE85") (pin "Q") (pinfunction "Q_Q") (pintype "output"))
      (node (ref "GATE89") (pin "C") (pinfunction "C_C") (pintype "input"))
    )
    (net (code "33") (name "MIN_TENS_SEG_F") (class "Default")
      (node (ref "D_BUS") (pin "25") (pinfunction "25_25") (pintype "passive"))
      (node (ref "GATE96") (pin "Q") (pinfunction "Q_Q") (pintype "output"))
    )
    (net (code "34") (name "MIN_TENS_SEG_G") (class "Default")
      (node (ref "D_BUS") (pin "26") (pinfunction "26_26") (pintype "passive"))
      (node (ref "GATE98") (pin "Q") (pinfunction "Q_Q") (pintype "output"))
    )
    (net (code "35") (name "MIN_UNIT_A") (class "Default")
      (node (ref "A_BUS") (pin "8") (pinfunction "8_8") (pintype "passive"))
      (node (ref "GATE50") (pin "A") (pinfunction "A_A") (pintype "input"))
      (node (ref "GATE56") (pin "A") (pinfunction "A_A") (pintype "input"))
      (node (ref "GATE59") (pin "A") (pinfunction "A_A") (pintype "input"))
      (node (ref "GATE61") (pin "A") (pinfunction "A_A") (pintype "input"))
      (node (ref "GATE63") (pin "A") (pinfunction "A_A") (pintype "input"))
    )
    (net (code "36") (name "MIN_UNIT_B") (class "Default")
      (node (ref "A_BUS") (pin "9") (pinfunction "9_9") (pintype "passive"))
      (node (ref "GATE51") (pin "A") (pinfunction "A_A") (pintype "input"))
      (node (ref "GATE56") (pin "B") (pinfunction "B_B") (pintype "input"))
      (node (ref "GATE60") (pin "A") (pinfunction "A_A") (pintype "input"))
      (node (ref "GATE61") (pin "B") (pinfunction "B_B") (pintype "input"))
      (node (ref "GATE62") (pin "A") (pinfunction "A_A") (pintype "input"))
      (node (ref "GATE65") (pin "A") (pinfunction "A_A") (pintype "input"))
    )
    (net (code "37") (name "MIN_UNIT_C") (class "Default")
      (node (ref "A_BUS") (pin "10") (pinfunction "10_10") (pintype "passive"))
      (node (ref "GATE52") (pin "A") (pinfunction "A_A") (pintype "input"))
      (node (ref "GATE56") (pin "C") (pinfunction "C_C") (pintype "input"))
      (node (ref "GATE57") (pin "A") (pinfunction "A_A") (pintype "input"))
      (node (ref "GATE60") (pin "B") (pinfunction "B_B") (pintype "input"))
      (node (ref "GATE62") (pin "B") (pinfunction "B_B") (pintype "input"))
    )
    (net (code "38") (name "MIN_UNIT_D") (class "Default")
      (node (ref "A_BUS") (pin "11") (pinfunction "11_11") (pintype "passive"))
      (node (ref "GATE53") (pin "A") (pinfunction "A_A") (pintype "input"))
      (node (ref "GATE54") (pin "A") (pinfunction "A_A") (pintype "input"))
      (node (ref "GATE57") (pin "B") (pinfunction "B_B") (pintype "input"))
      (node (ref "GATE59") (pin "B") (pinfunction "B_B") (pintype "input"))
      (node (ref "GATE64") (pin "A") (pinfunction "A_A") (pintype "input"))
    )
    (net (code "39") (name "MIN_UNIT_SEG_A") (class "Default")
      (node (ref "D_BUS") (pin "14") (pinfunction "14_14") (pintype "passive"))
      (node (ref "GATE67") (pin "Q") (pinfunction "Q_Q") (pintype "output"))
    )
    (net (code "40") (name "MIN_UNIT_SEG_B") (class "Default")
      (node (ref "D_BUS") (pin "15") (pinfunction "15_15") (pintype "passive"))
      (node (ref "GATE69") (pin "Q") (pinfunction "Q_Q") (pintype "output"))
    )
    (net (code "41") (name "MIN_UNIT_SEG_C") (class "Default")
      (node (ref "D_BUS") (pin "16") (pinfunction "16_16") (pintype "passive"))
      (node (ref "GATE71") (pin "Q") (pinfunction "Q_Q") (pintype "output"))
    )
    (net (code "42") (name "MIN_UNIT_SEG_D") (class "Default")
      (node (ref "D_BUS") (pin "17") (pinfunction "17_17") (pintype "passive"))
      (node (ref "GATE73") (pin "Q") (pinfunction "Q_Q") (pintype "output"))
    )
    (net (code "43") (name "MIN_UNIT_SEG_E") (class "Default")
      (node (ref "D_BUS") (pin "18") (pinfunction "18_18") (pintype "passive"))
      (node (ref "GATE75") (pin "Q") (pinfunction "Q_Q") (pintype "output"))
    )
    (net (code "44") (name "MIN_UNIT_SEG_F") (class "Default")
      (node (ref "D_BUS") (pin "19") (pinfunction "19_19") (pintype "passive"))
      (node (ref "GATE77") (pin "Q") (pinfunction "Q_Q") (pintype "output"))
    )
    (net (code "45") (name "MIN_UNIT_SEG_G") (class "Default")
      (node (ref "D_BUS") (pin "20") (pinfunction "20_20") (pintype "passive"))
      (node (ref "GATE79") (pin "Q") (pinfunction "Q_Q") (pintype "output"))
    )
    (net (code "46") (name "Net-(GATE1-PadQ)") (class "Default")
      (node (ref "GATE1") (pin "Q") (pinfunction "Q_Q") (pintype "output"))
      (node (ref "GATE13") (pin "C") (pinfunction "C_C") (pintype "input"))
      (node (ref "GATE15") (pin "B") (pinfunction "B_B") (pintype "input"))
      (node (ref "GATE16") (pin "B") (pinfunction "B_B") (pintype "input"))
      (node (ref "GATE9") (pin "A") (pinfunction "A_A") (pintype "input"))
    )
    (net (code "47") (name "Net-(GATE3-PadQ)") (class "Default")
      (node (ref "GATE3") (pin "Q") (pinfunction "Q_Q") (pintype "output"))
      (node (ref "GATE5") (pin "B") (pinfunction "B_B") (pintype "input"))
    )
    (net (code "48") (name "Net-(GATE5-PadQ)") (class "Default")
      (node (ref "GATE5") (pin "Q") (pinfunction "Q_Q") (pintype "output"))
      (node (ref "GATE6") (pin "A") (pinfunction "A_A") (pintype "input"))
    )
    (net (code "49") (name "Net-(GATE10-PadC)") (class "Default")
      (node (ref "GATE10") (pin "C") (pinfunction "C_C") (pintype "input"))
      (node (ref "GATE15") (pin "C") (pinfunction "C_C") (pintype "input"))
      (node (ref "GATE2") (pin "Q") (pinfunction "Q_Q") (pintype "output"))
      (node (ref "GATE8") (pin "C") (pinfunction "C_C") (pintype "input"))
    )
    (net (code "50") (name "Net-(GATE10-PadQ)") (class "Default")
      (node (ref "GATE10") (pin "Q") (pinfunction "Q_Q") (pintype "output"))
      (node (ref "GATE17") (pin "D") (pinfunction "D_D") (pintype "input"))
      (node (ref "GATE23") (pin "C") (pinfunction "C_C") (pintype "input"))
      (node (ref "GATE25") (pin "B") (pinfunction "B_B") (pintype "input"))
    )
    (net (code "51") (name "Net-(GATE11-PadC)") (class "Default")
      (node (ref "GATE11") (pin "C") (pinfunction "C_C") (pintype "input"))
      (node (ref "GATE4") (pin "Q") (pinfunction "Q_Q") (pintype "output"))
    )
    (net (code "52") (name "Net-(GATE11-PadQ)") (class "Default")
      (node (ref "GATE11") (pin "Q") (pinfunction "Q_Q") (pintype "output"))
      (node (ref "GATE17") (pin "E") (pinfunction "E_E") (pintype "input"))
      (node (ref "GATE23") (pin "D") (pinfunction "D_D") (pintype "input"))
      (node (ref "GATE27") (pin "B") (pinfunction "B_B") (pintype "input"))
      (node (ref "GATE29") (pin "B") (pinfunction "B_B") (pintype "input"))
    )
    (net (code "53") (name "Net-(GATE12-PadC)") (class "Default")
      (node (ref "GATE12") (pin "C") (pinfunction "C_C") (pintype "input"))
      (node (ref "GATE14") (pin "B") (pinfunction "B_B") (pintype "input"))
      (node (ref "GATE16") (pin "C") (pinfunction "C_C") (pintype "input"))
      (node (ref "GATE6") (pin "Q") (pinfunction "Q_Q") (pintype "output"))
      (node (ref "GATE9") (pin "B") (pinfunction "B_B") (pintype "input"))
    )
    (net (code "54") (name "Net-(GATE12-PadQ)") (class "Default")
      (node (ref "GATE12") (pin "Q") (pinfunction "Q_Q") (pintype "output"))
      (node (ref "GATE19") (pin "C") (pinfunction "C_C") (pintype "input"))
    )
    (net (code "55") (name "Net-(GATE13-PadQ)") (class "Default")
      (node (ref "GATE13") (pin "Q") (pinfunction "Q_Q") (pintype "output"))
      (node (ref "GATE19") (pin "D") (pinfunction "D_D") (pintype "input"))
      (node (ref "GATE21") (pin "C") (pinfunction "C_C") (pintype "input"))
    )
    (net (code "56") (name "Net-(GATE14-PadQ)") (class "Default")
      (node (ref "GATE14") (pin "Q") (pinfunction "Q_Q") (pintype "output"))
      (node (ref "GATE21") (pin "D") (pinfunction "D_D") (pintype "input"))
      (node (ref "GATE27") (pin "C") (pinfunction "C_C") (pintype "input"))
      (node (ref "GATE29") (pin "C") (pinfunction "C_C") (pintype "input"))
    )
    (net (code "57") (name "Net-(GATE15-PadQ)") (class "Default")
      (node (ref "GATE15") (pin "Q") (pinfunction "Q_Q") (pintype "output"))
      (node (ref "GATE19") (pin "E") (pinfunction "E_E") (pintype "input"))
      (node (ref "GATE21") (pin "E") (pinfunction "E_E") (pintype "input"))
    )
    (net (code "58") (name "Net-(GATE16-PadQ)") (class "Default")
      (node (ref "GATE16") (pin "Q") (pinfunction "Q_Q") (pintype "output"))
      (node (ref "GATE23") (pin "E") (pinfunction "E_E") (pintype "input"))
      (node (ref "GATE27") (pin "D") (pinfunction "D_D") (pintype "input"))
      (node (ref "GATE29") (pin "D") (pinfunction "D_D") (pintype "input"))
    )
    (net (code "59") (name "Net-(GATE17-PadA)") (class "Default")
      (node (ref "GATE17") (pin "A") (pinfunction "A_A") (pintype "input"))
      (node (ref "GATE19") (pin "A") (pinfunction "A_A") (pintype "input"))
      (node (ref "GATE21") (pin "A") (pinfunction "A_A") (pintype "input"))
      (node (ref "GATE23") (pin "A") (pinfunction "A_A") (pintype "input"))
      (node (ref "GATE25") (pin "A") (pinfunction "A_A") (pintype "input"))
      (node (ref "GATE27") (pin "A") (pinfunction "A_A") (pintype "input"))
      (node (ref "GATE7") (pin "Q") (pinfunction "Q_Q") (pintype "output"))
    )
    (net (code "60") (name "Net-(GATE17-PadB)") (class "Default")
      (node (ref "GATE17") (pin "B") (pinfunction "B_B") (pintype "input"))
      (node (ref "GATE19") (pin "B") (pinfunction "B_B") (pintype "input"))
      (node (ref "GATE23") (pin "B") (pinfunction "B_B") (pintype "input"))
      (node (ref "GATE29") (pin "A") (pinfunction "A_A") (pintype "input"))
      (node (ref "GATE8") (pin "Q") (pinfunction "Q_Q") (pintype "output"))
    )
    (net (code "61") (name "Net-(GATE17-PadC)") (class "Default")
      (node (ref "GATE17") (pin "C") (pinfunction "C_C") (pintype "input"))
      (node (ref "GATE21") (pin "B") (pinfunction "B_B") (pintype "input"))
      (node (ref "GATE9") (pin "Q") (pinfunction "Q_Q") (pintype "output"))
    )
    (net (code "62") (name "Net-(GATE17-PadQ)") (class "Default")
      (node (ref "GATE17") (pin "Q") (pinfunction "Q_Q") (pintype "output"))
      (node (ref "GATE18") (pin "A") (pinfunction "A_A") (pintype "input"))
    )
    (net (code "63") (name "Net-(GATE19-PadQ)") (class "Default")
      (node (ref "GATE19") (pin "Q") (pinfunction "Q_Q") (pintype "output"))
      (node (ref "GATE20") (pin "A") (pinfunction "A_A") (pintype "input"))
    )
    (net (code "64") (name "Net-(GATE21-PadQ)") (class "Default")
      (node (ref "GATE21") (pin "Q") (pinfunction "Q_Q") (pintype "output"))
      (node (ref "GATE22") (pin "A") (pinfunction "A_A") (pintype "input"))
    )
    (net (code "65") (name "Net-(GATE23-PadQ)") (class "Default")
      (node (ref "GATE23") (pin "Q") (pinfunction "Q_Q") (pintype "output"))
      (node (ref "GATE24") (pin "A") (pinfunction "A_A") (pintype "input"))
    )
    (net (code "66") (name "Net-(GATE25-PadQ)") (class "Default")
      (node (ref "GATE25") (pin "Q") (pinfunction "Q_Q") (pintype "output"))
      (node (ref "GATE26") (pin "A") (pinfunction "A_A") (pintype "input"))
    )
    (net (code "67") (name "Net-(GATE27-PadQ)") (class "Default")
      (node (ref "GATE27") (pin "Q") (pinfunction "Q_Q") (pintype "output"))
      (node (ref "GATE28") (pin "A") (pinfunction "A_A") (pintype "input"))
    )
    (net (code "68") (name "Net-(GATE29-PadQ)") (class "Default")
      (node (ref "GATE29") (pin "Q") (pinfunction "Q_Q") (pintype "output"))
      (node (ref "GATE30") (pin "A") (pinfunction "A_A") (pintype "input"))
    )
    (net (code "69") (name "Net-(GATE31-PadQ)") (class "Default")
      (node (ref "GATE31") (pin "Q") (pinfunction "Q_Q") (pintype "output"))
      (node (ref "GATE34") (pin "B") (pinfunction "B_B") (pintype "input"))
      (node (ref "GATE38") (pin "B") (pinfunction "B_B") (pintype "input"))
    )
    (net (code "70") (name "Net-(GATE32-PadQ)") (class "Default")
      (node (ref "GATE32") (pin "Q") (pinfunction "Q_Q") (pintype "output"))
      (node (ref "GATE35") (pin "B") (pinfunction "B_B") (pintype "input"))
      (node (ref "GATE44") (pin "B") (pinfunction "B_B") (pintype "input"))
    )
    (net (code "71") (name "Net-(GATE33-PadQ)") (class "Default")
      (node (ref "GATE33") (pin "Q") (pinfunction "Q_Q") (pintype "output"))
      (node (ref "GATE34") (pin "C") (pinfunction "C_C") (pintype "input"))
      (node (ref "GATE39") (pin "B") (pinfunction "B_B") (pintype "input"))
      (node (ref "GATE42") (pin "B") (pinfunction "B_B") (pintype "input"))
    )
    (net (code "72") (name "Net-(GATE34-PadQ)") (class "Default")
      (node (ref "GATE34") (pin "Q") (pinfunction "Q_Q") (pintype "output"))
      (node (ref "GATE40") (pin "A") (pinfunction "A_A") (pintype "input"))
    )
    (net (code "73") (name "Net-(GATE35-PadQ)") (class "Default")
      (node (ref "GATE35") (pin "Q") (pinfunction "Q_Q") (pintype "output"))
      (node (ref "GATE40") (pin "B") (pinfunction "B_B") (pintype "input"))
      (node (ref "GATE48") (pin "A") (pinfunction "A_A") (pintype "input"))
    )
    (net (code "74") (name "Net-(GATE37-PadQ)") (class "Default")
      (node (ref "GATE37") (pin "Q") (pinfunction "Q_Q") (pintype "output"))
      (node (ref "GATE42") (pin "A") (pinfunction "A_A") (pintype "input"))
      (node (ref "GATE46") (pin "A") (pinfunction "A_A") (pintype "input"))
    )
    (net (code "75") (name "Net-(GATE38-PadQ)") (class "Default")
      (node (ref "GATE38") (pin "Q") (pinfunction "Q_Q") (pintype "output"))
      (node (ref "GATE44") (pin "A") (pinfunction "A_A") (pintype "input"))
    )
    (net (code "76") (name "Net-(GATE39-PadQ)") (class "Default")
      (node (ref "GATE39") (pin "Q") (pinfunction "Q_Q") (pintype "output"))
      (node (ref "GATE46") (pin "B") (pinfunction "B_B") (pintype "input"))
      (node (ref "GATE48") (pin "B") (pinfunction "B_B") (pintype "input"))
    )
    (net (code "77") (name "Net-(GATE40-PadQ)") (class "Default")
      (node (ref "GATE40") (pin "Q") (pinfunction "Q_Q") (pintype "output"))
      (node (ref "GATE41") (pin "A") (pinfunction "A_A") (pintype "input"))
    )
    (net (code "78") (name "Net-(GATE42-PadQ)") (class "Default")
      (node (ref "GATE42") (pin "Q") (pinfunction "Q_Q") (pintype "output"))
      (node (ref "GATE43") (pin "A") (pinfunction "A_A") (pintype "input"))
    )
    (net (code "79") (name "Net-(GATE44-PadQ)") (class "Default")
      (node (ref "GATE44") (pin "Q") (pinfunction "Q_Q") (pintype "output"))
      (node (ref "GATE45") (pin "A") (pinfunction "A_A") (pintype "input"))
    )
    (net (code "80") (name "Net-(GATE46-PadQ)") (class "Default")
      (node (ref "GATE46") (pin "Q") (pinfunction "Q_Q") (pintype "output"))
      (node (ref "GATE47") (pin "A") (pinfunction "A_A") (pintype "input"))
    )
    (net (code "81") (name "Net-(GATE48-PadQ)") (class "Default")
      (node (ref "GATE48") (pin "Q") (pinfunction "Q_Q") (pintype "output"))
      (node (ref "GATE49") (pin "A") (pinfunction "A_A") (pintype "input"))
    )
    (net (code "82") (name "Net-(GATE50-PadQ)") (class "Default")
      (node (ref "GATE50") (pin "Q") (pinfunction "Q_Q") (pintype "output"))
      (node (ref "GATE58") (pin "A") (pinfunction "A_A") (pintype "input"))
      (node (ref "GATE62") (pin "C") (pinfunction "C_C") (pintype "input"))
      (node (ref "GATE64") (pin "B") (pinfunction "B_B") (pintype "input"))
      (node (ref "GATE65") (pin "B") (pinfunction "B_B") (pintype "input"))
    )
    (net (code "83") (name "Net-(GATE51-PadQ)") (class "Default")
      (node (ref "GATE51") (pin "Q") (pinfunction "Q_Q") (pintype "output"))
      (node (ref "GATE57") (pin "C") (pinfunction "C_C") (pintype "input"))
      (node (ref "GATE59") (pin "C") (pinfunction "C_C") (pintype "input"))
      (node (ref "GATE64") (pin "C") (pinfunction "C_C") (pintype "input"))
    )
    (net (code "84") (name "Net-(GATE52-PadQ)") (class "Default")
      (node (ref "GATE52") (pin "Q") (pinfunction "Q_Q") (pintype "output"))
      (node (ref "GATE54") (pin "B") (pinfunction "B_B") (pintype "input"))
    )
    (net (code "85") (name "Net-(GATE53-PadQ)") (class "Default")
      (node (ref "GATE53") (pin "Q") (pinfunction "Q_Q") (pintype "output"))
      (node (ref "GATE60") (pin "C") (pinfunction "C_C") (pintype "input"))
    )
    (net (code "86") (name "Net-(GATE54-PadQ)") (class "Default")
      (node (ref "GATE54") (pin "Q") (pinfunction "Q_Q") (pintype "output"))
      (node (ref "GATE55") (pin "A") (pinfunction "A_A") (pintype "input"))
    )
    (net (code "87") (name "Net-(GATE55-PadQ)") (class "Default")
      (node (ref "GATE55") (pin "Q") (pinfunction "Q_Q") (pintype "output"))
      (node (ref "GATE58") (pin "B") (pinfunction "B_B") (pintype "input"))
      (node (ref "GATE61") (pin "C") (pinfunction "C_C") (pintype "input"))
      (node (ref "GATE63") (pin "B") (pinfunction "B_B") (pintype "input"))
      (node (ref "GATE65") (pin "C") (pinfunction "C_C") (pintype "input"))
    )
    (net (code "88") (name "Net-(GATE56-PadQ)") (class "Default")
      (node (ref "GATE56") (pin "Q") (pinfunction "Q_Q") (pintype "output"))
      (node (ref "GATE66") (pin "A") (pinfunction "A_A") (pintype "input"))
      (node (ref "GATE68") (pin "A") (pinfunction "A_A") (pintype "input"))
      (node (ref "GATE70") (pin "A") (pinfunction "A_A") (pintype "input"))
      (node (ref "GATE72") (pin "A") (pinfunction "A_A") (pintype "input"))
      (node (ref "GATE74") (pin "A") (pinfunction "A_A") (pintype "input"))
      (node (ref "GATE76") (pin "A") (pinfunction "A_A") (pintype "input"))
    )
    (net (code "89") (name "Net-(GATE57-PadQ)") (class "Default")
      (node (ref "GATE57") (pin "Q") (pinfunction "Q_Q") (pintype "output"))
      (node (ref "GATE66") (pin "B") (pinfunction "B_B") (pintype "input"))
      (node (ref "GATE68") (pin "B") (pinfunction "B_B") (pintype "input"))
      (node (ref "GATE72") (pin "B") (pinfunction "B_B") (pintype "input"))
      (node (ref "GATE78") (pin "A") (pinfunction "A_A") (pintype "input"))
    )
    (net (code "90") (name "Net-(GATE58-PadQ)") (class "Default")
      (node (ref "GATE58") (pin "Q") (pinfunction "Q_Q") (pintype "output"))
      (node (ref "GATE66") (pin "C") (pinfunction "C_C") (pintype "input"))
      (node (ref "GATE70") (pin "B") (pinfunction "B_B") (pintype "input"))
    )
    (net (code "91") (name "Net-(GATE59-PadQ)") (class "Default")
      (node (ref "GATE59") (pin "Q") (pinfunction "Q_Q") (pintype "output"))
      (node (ref "GATE66") (pin "D") (pinfunction "D_D") (pintype "input"))
      (node (ref "GATE72") (pin "C") (pinfunction "C_C") (pintype "input"))
      (node (ref "GATE74") (pin "B") (pinfunction "B_B") (pintype "input"))
    )
    (net (code "92") (name "Net-(GATE60-PadQ)") (class "Default")
      (node (ref "GATE60") (pin "Q") (pinfunction "Q_Q") (pintype "output"))
      (node (ref "GATE66") (pin "E") (pinfunction "E_E") (pintype "input"))
      (node (ref "GATE72") (pin "D") (pinfunction "D_D") (pintype "input"))
      (node (ref "GATE76") (pin "B") (pinfunction "B_B") (pintype "input"))
      (node (ref "GATE78") (pin "B") (pinfunction "B_B") (pintype "input"))
    )
    (net (code "93") (name "Net-(GATE61-PadQ)") (class "Default")
      (node (ref "GATE61") (pin "Q") (pinfunction "Q_Q") (pintype "output"))
      (node (ref "GATE68") (pin "C") (pinfunction "C_C") (pintype "input"))
    )
    (net (code "94") (name "Net-(GATE62-PadQ)") (class "Default")
      (node (ref "GATE62") (pin "Q") (pinfunction "Q_Q") (pintype "output"))
      (node (ref "GATE68") (pin "D") (pinfunction "D_D") (pintype "input"))
      (node (ref "GATE70") (pin "C") (pinfunction "C_C") (pintype "input"))
    )
    (net (code "95") (name "Net-(GATE63-PadQ)") (class "Default")
      (node (ref "GATE63") (pin "Q") (pinfunction "Q_Q") (pintype "output"))
      (node (ref "GATE70") (pin "D") (pinfunction "D_D") (pintype "input"))
      (node (ref "GATE76") (pin "C") (pinfunction "C_C") (pintype "input"))
      (node (ref "GATE78") (pin "C") (pinfunction "C_C") (pintype "input"))
    )
    (net (code "96") (name "Net-(GATE64-PadQ)") (class "Default")
      (node (ref "GATE64") (pin "Q") (pinfunction "Q_Q") (pintype "output"))
      (node (ref "GATE68") (pin "E") (pinfunction "E_E") (pintype "input"))
      (node (ref "GATE70") (pin "E") (pinfunction "E_E") (pintype "input"))
    )
    (net (code "97") (name "Net-(GATE65-PadQ)") (class "Default")
      (node (ref "GATE65") (pin "Q") (pinfunction "Q_Q") (pintype "output"))
      (node (ref "GATE72") (pin "E") (pinfunction "E_E") (pintype "input"))
      (node (ref "GATE76") (pin "D") (pinfunction "D_D") (pintype "input"))
      (node (ref "GATE78") (pin "D") (pinfunction "D_D") (pintype "input"))
    )
    (net (code "98") (name "Net-(GATE66-PadQ)") (class "Default")
      (node (ref "GATE66") (pin "Q") (pinfunction "Q_Q") (pintype "output"))
      (node (ref "GATE67") (pin "A") (pinfunction "A_A") (pintype "input"))
    )
    (net (code "99") (name "Net-(GATE68-PadQ)") (class "Default")
      (node (ref "GATE68") (pin "Q") (pinfunction "Q_Q") (pintype "output"))
      (node (ref "GATE69") (pin "A") (pinfunction "A_A") (pintype "input"))
    )
    (net (code "100") (name "Net-(GATE70-PadQ)") (class "Default")
      (node (ref "GATE70") (pin "Q") (pinfunction "Q_Q") (pintype "output"))
      (node (ref "GATE71") (pin "A") (pinfunction "A_A") (pintype "input"))
    )
    (net (code "101") (name "Net-(GATE72-PadQ)") (class "Default")
      (node (ref "GATE72") (pin "Q") (pinfunction "Q_Q") (pintype "output"))
      (node (ref "GATE73") (pin "A") (pinfunction "A_A") (pintype "input"))
    )
    (net (code "102") (name "Net-(GATE74-PadQ)") (class "Default")
      (node (ref "GATE74") (pin "Q") (pinfunction "Q_Q") (pintype "output"))
      (node (ref "GATE75") (pin "A") (pinfunction "A_A") (pintype "input"))
    )
    (net (code "103") (name "Net-(GATE76-PadQ)") (class "Default")
      (node (ref "GATE76") (pin "Q") (pinfunction "Q_Q") (pintype "output"))
      (node (ref "GATE77") (pin "A") (pinfunction "A_A") (pintype "input"))
    )
    (net (code "104") (name "Net-(GATE78-PadQ)") (class "Default")
      (node (ref "GATE78") (pin "Q") (pinfunction "Q_Q") (pintype "output"))
      (node (ref "GATE79") (pin "A") (pinfunction "A_A") (pintype "input"))
    )
    (net (code "105") (name "Net-(GATE80-PadQ)") (class "Default")
      (node (ref "GATE80") (pin "Q") (pinfunction "Q_Q") (pintype "output"))
      (node (ref "GATE83") (pin "B") (pinfunction "B_B") (pintype "input"))
      (node (ref "GATE87") (pin "B") (pinfunction "B_B") (pintype "input"))
    )
    (net (code "106") (name "Net-(GATE81-PadQ)") (class "Default")
      (node (ref "GATE81") (pin "Q") (pinfunction "Q_Q") (pintype "output"))
      (node (ref "GATE84") (pin "B") (pinfunction "B_B") (pintype "input"))
      (node (ref "GATE93") (pin "B") (pinfunction "B_B") (pintype "input"))
    )
    (net (code "107") (name "Net-(GATE82-PadQ)") (class "Default")
      (node (ref "GATE82") (pin "Q") (pinfunction "Q_Q") (pintype "output"))
      (node (ref "GATE83") (pin "C") (pinfunction "C_C") (pintype "input"))
      (node (ref "GATE88") (pin "B") (pinfunction "B_B") (pintype "input"))
      (node (ref "GATE91") (pin "B") (pinfunction "B_B") (pintype "input"))
    )
    (net (code "108") (name "Net-(GATE83-PadQ)") (class "Default")
      (node (ref "GATE83") (pin "Q") (pinfunction "Q_Q") (pintype "output"))
      (node (ref "GATE89") (pin "A") (pinfunction "A_A") (pintype "input"))
    )
    (net (code "109") (name "Net-(GATE84-PadQ)") (class "Default")
      (node (ref "GATE84") (pin "Q") (pinfunction "Q_Q") (pintype "output"))
      (node (ref "GATE89") (pin "B") (pinfunction "B_B") (pintype "input"))
      (node (ref "GATE97") (pin "A") (pinfunction "A_A") (pintype "input"))
    )
    (net (code "110") (name "Net-(GATE86-PadQ)") (class "Default")
      (node (ref "GATE86") (pin "Q") (pinfunction "Q_Q") (pintype "output"))
      (node (ref "GATE91") (pin "A") (pinfunction "A_A") (pintype "input"))
      (node (ref "GATE95") (pin "A") (pinfunction "A_A") (pintype "input"))
    )
    (net (code "111") (name "Net-(GATE87-PadQ)") (class "Default")
      (node (ref "GATE87") (pin "Q") (pinfunction "Q_Q") (pintype "output"))
      (node (ref "GATE93") (pin "A") (pinfunction "A_A") (pintype "input"))
    )
    (net (code "112") (name "Net-(GATE88-PadQ)") (class "Default")
      (node (ref "GATE88") (pin "Q") (pinfunction "Q_Q") (pintype "output"))
      (node (ref "GATE95") (pin "B") (pinfunction "B_B") (pintype "input"))
      (node (ref "GATE97") (pin "B") (pinfunction "B_B") (pintype "input"))
    )
    (net (code "113") (name "Net-(GATE89-PadQ)") (class "Default")
      (node (ref "GATE89") (pin "Q") (pinfunction "Q_Q") (pintype "output"))
      (node (ref "GATE90") (pin "A") (pinfunction "A_A") (pintype "input"))
    )
    (net (code "114") (name "Net-(GATE91-PadQ)") (class "Default")
      (node (ref "GATE91") (pin "Q") (pinfunction "Q_Q") (pintype "output"))
      (node (ref "GATE92") (pin "A") (pinfunction "A_A") (pintype "input"))
    )
    (net (code "115") (name "Net-(GATE93-PadQ)") (class "Default")
      (node (ref "GATE93") (pin "Q") (pinfunction "Q_Q") (pintype "output"))
      (node (ref "GATE94") (pin "A") (pinfunction "A_A") (pintype "input"))
    )
    (net (code "116") (name "Net-(GATE95-PadQ)") (class "Default")
      (node (ref "GATE95") (pin "Q") (pinfunction "Q_Q") (pintype "output"))
      (node (ref "GATE96") (pin "A") (pinfunction "A_A") (pintype "input"))
    )
    (net (code "117") (name "Net-(GATE97-PadQ)") (class "Default")
      (node (ref "GATE97") (pin "Q") (pinfunction "Q_Q") (pintype "output"))
      (node (ref "GATE98") (pin "A") (pinfunction "A_A") (pintype "input"))
    )
    (net (code "118") (name "Net-(GATE100-PadQ)") (class "Default")
      (node (ref "GATE100") (pin "Q") (pinfunction "Q_Q") (pintype "output"))
      (node (ref "GATE106") (pin "C") (pinfunction "C_C") (pintype "input"))
      (node (ref "GATE108") (pin "C") (pinfunction "C_C") (pintype "input"))
      (node (ref "GATE113") (pin "C") (pinfunction "C_C") (pintype "input"))
    )
    (net (code "119") (name "Net-(GATE101-PadQ)") (class "Default")
      (node (ref "GATE101") (pin "Q") (pinfunction "Q_Q") (pintype "output"))
      (node (ref "GATE103") (pin "B") (pinfunction "B_B") (pintype "input"))
    )
    (net (code "120") (name "Net-(GATE102-PadQ)") (class "Default")
      (node (ref "GATE102") (pin "Q") (pinfunction "Q_Q") (pintype "output"))
      (node (ref "GATE109") (pin "C") (pinfunction "C_C") (pintype "input"))
    )
    (net (code "121") (name "Net-(GATE103-PadQ)") (class "Default")
      (node (ref "GATE103") (pin "Q") (pinfunction "Q_Q") (pintype "output"))
      (node (ref "GATE104") (pin "A") (pinfunction "A_A") (pintype "input"))
    )
    (net (code "122") (name "Net-(GATE104-PadQ)") (class "Default")
      (node (ref "GATE104") (pin "Q") (pinfunction "Q_Q") (pintype "output"))
      (node (ref "GATE107") (pin "B") (pinfunction "B_B") (pintype "input"))
      (node (ref "GATE110") (pin "C") (pinfunction "C_C") (pintype "input"))
      (node (ref "GATE112") (pin "B") (pinfunction "B_B") (pintype "input"))
      (node (ref "GATE114") (pin "C") (pinfunction "C_C") (pintype "input"))
    )
    (net (code "123") (name "Net-(GATE105-PadQ)") (class "Default")
      (node (ref "GATE105") (pin "Q") (pinfunction "Q_Q") (pintype "output"))
      (node (ref "GATE115") (pin "A") (pinfunction "A_A") (pintype "input"))
      (node (ref "GATE117") (pin "A") (pinfunction "A_A") (pintype "input"))
      (node (ref "GATE119") (pin "A") (pinfunction "A_A") (pintype "input"))
      (node (ref "GATE121") (pin "A") (pinfunction "A_A") (pintype "input"))
      (node (ref "GATE123") (pin "A") (pinfunction "A_A") (pintype "input"))
      (node (ref "GATE125") (pin "A") (pinfunction "A_A") (pintype "input"))
    )
    (net (code "124") (name "Net-(GATE106-PadQ)") (class "Default")
      (node (ref "GATE106") (pin "Q") (pinfunction "Q_Q") (pintype "output"))
      (node (ref "GATE115") (pin "B") (pinfunction "B_B") (pintype "input"))
      (node (ref "GATE117") (pin "B") (pinfunction "B_B") (pintype "input"))
      (node (ref "GATE121") (pin "B") (pinfunction "B_B") (pintype "input"))
      (node (ref "GATE127") (pin "A") (pinfunction "A_A") (pintype "input"))
    )
    (net (code "125") (name "Net-(GATE107-PadA)") (class "Default")
      (node (ref "GATE107") (pin "A") (pinfunction "A_A") (pintype "input"))
      (node (ref "GATE111") (pin "C") (pinfunction "C_C") (pintype "input"))
      (node (ref "GATE113") (pin "B") (pinfunction "B_B") (pintype "input"))
      (node (ref "GATE114") (pin "B") (pinfunction "B_B") (pintype "input"))
      (node (ref "GATE99") (pin "Q") (pinfunction "Q_Q") (pintype "output"))
    )
    (net (code "126") (name "Net-(GATE107-PadQ)") (class "Default")
      (node (ref "GATE107") (pin "Q") (pinfunction "Q_Q") (pintype "output"))
      (node (ref "GATE115") (pin "C") (pinfunction "C_C") (pintype "input"))
      (node (ref "GATE119") (pin "B") (pinfunction "B_B") (pintype "input"))
    )
    (net (code "127") (name "Net-(GATE108-PadQ)") (class "Default")
      (node (ref "GATE108") (pin "Q") (pinfunction "Q_Q") (pintype "output"))
      (node (ref "GATE115") (pin "D") (pinfunction "D_D") (pintype "input"))
      (node (ref "GATE121") (pin "C") (pinfunction "C_C") (pintype "input"))
      (node (ref "GATE123") (pin "B") (pinfunction "B_B") (pintype "input"))
    )
    (net (code "128") (name "Net-(GATE109-PadQ)") (class "Default")
      (node (ref "GATE109") (pin "Q") (pinfunction "Q_Q") (pintype "output"))
      (node (ref "GATE115") (pin "E") (pinfunction "E_E") (pintype "input"))
      (node (ref "GATE121") (pin "D") (pinfunction "D_D") (pintype "input"))
      (node (ref "GATE125") (pin "B") (pinfunction "B_B") (pintype "input"))
      (node (ref "GATE127") (pin "B") (pinfunction "B_B") (pintype "input"))
    )
    (net (code "129") (name "Net-(GATE110-PadQ)") (class "Default")
      (node (ref "GATE110") (pin "Q") (pinfunction "Q_Q") (pintype "output"))
      (node (ref "GATE117") (pin "C") (pinfunction "C_C") (pintype "input"))
    )
    (net (code "130") (name "Net-(GATE111-PadQ)") (class "Default")
      (node (ref "GATE111") (pin "Q") (pinfunction "Q_Q") (pintype "output"))
      (node (ref "GATE117") (pin "D") (pinfunction "D_D") (pintype "input"))
      (node (ref "GATE119") (pin "C") (pinfunction "C_C") (pintype "input"))
    )
    (net (code "131") (name "Net-(GATE112-PadQ)") (class "Default")
      (node (ref "GATE112") (pin "Q") (pinfunction "Q_Q") (pintype "output"))
      (node (ref "GATE119") (pin "D") (pinfunction "D_D") (pintype "input"))
      (node (ref "GATE125") (pin "C") (pinfunction "C_C") (pintype "input"))
      (node (ref "GATE127") (pin "C") (pinfunction "C_C") (pintype "input"))
    )
    (net (code "132") (name "Net-(GATE113-PadQ)") (class "Default")
      (node (ref "GATE113") (pin "Q") (pinfunction "Q_Q") (pintype "output"))
      (node (ref "GATE117") (pin "E") (pinfunction "E_E") (pintype "input"))
      (node (ref "GATE119") (pin "E") (pinfunction "E_E") (pintype "input"))
    )
    (net (code "133") (name "Net-(GATE114-PadQ)") (class "Default")
      (node (ref "GATE114") (pin "Q") (pinfunction "Q_Q") (pintype "output"))
      (node (ref "GATE121") (pin "E") (pinfunction "E_E") (pintype "input"))
      (node (ref "GATE125") (pin "D") (pinfunction "D_D") (pintype "input"))
      (node (ref "GATE127") (pin "D") (pinfunction "D_D") (pintype "input"))
    )
    (net (code "134") (name "Net-(GATE115-PadQ)") (class "Default")
      (node (ref "GATE115") (pin "Q") (pinfunction "Q_Q") (pintype "output"))
      (node (ref "GATE116") (pin "A") (pinfunction "A_A") (pintype "input"))
    )
    (net (code "135") (name "Net-(GATE117-PadQ)") (class "Default")
      (node (ref "GATE117") (pin "Q") (pinfunction "Q_Q") (pintype "output"))
      (node (ref "GATE118") (pin "A") (pinfunction "A_A") (pintype "input"))
    )
    (net (code "136") (name "Net-(GATE119-PadQ)") (class "Default")
      (node (ref "GATE119") (pin "Q") (pinfunction "Q_Q") (pintype "output"))
      (node (ref "GATE120") (pin "A") (pinfunction "A_A") (pintype "input"))
    )
    (net (code "137") (name "Net-(GATE121-PadQ)") (class "Default")
      (node (ref "GATE121") (pin "Q") (pinfunction "Q_Q") (pintype "output"))
      (node (ref "GATE122") (pin "A") (pinfunction "A_A") (pintype "input"))
    )
    (net (code "138") (name "Net-(GATE123-PadQ)") (class "Default")
      (node (ref "GATE123") (pin "Q") (pinfunction "Q_Q") (pintype "output"))
      (node (ref "GATE124") (pin "A") (pinfunction "A_A") (pintype "input"))
    )
    (net (code "139") (name "Net-(GATE125-PadQ)") (class "Default")
      (node (ref "GATE125") (pin "Q") (pinfunction "Q_Q") (pintype "output"))
      (node (ref "GATE126") (pin "A") (pinfunction "A_A") (pintype "input"))
    )
    (net (code "140") (name "Net-(GATE127-PadQ)") (class "Default")
      (node (ref "GATE127") (pin "Q") (pinfunction "Q_Q") (pintype "output"))
      (node (ref "GATE128") (pin "A") (pinfunction "A_A") (pintype "input"))
    )
    (net (code "141") (name "Net-(GATE129-PadQ)") (class "Default")
      (node (ref "GATE129") (pin "Q") (pinfunction "Q_Q") (pintype "output"))
      (node (ref "GATE131") (pin "A") (pinfunction "A_A") (pintype "input"))
    )
    (net (code "142") (name "Net-(GATE130-PadQ)") (class "Default")
      (node (ref "GATE130") (pin "Q") (pinfunction "Q_Q") (pintype "output"))
      (node (ref "GATE133") (pin "B") (pinfunction "B_B") (pintype "input"))
      (node (ref "GATE137") (pin "A") (pinfunction "A_A") (pintype "input"))
    )
    (net (code "143") (name "Net-(GATE131-PadQ)") (class "Default")
      (node (ref "GATE131") (pin "Q") (pinfunction "Q_Q") (pintype "output"))
      (node (ref "GATE132") (pin "A") (pinfunction "A_A") (pintype "input"))
    )
    (net (code "144") (name "Net-(GATE133-PadQ)") (class "Default")
      (node (ref "GATE133") (pin "Q") (pinfunction "Q_Q") (pintype "output"))
      (node (ref "GATE134") (pin "A") (pinfunction "A_A") (pintype "input"))
    )
    (net (code "145") (name "SEC_TENS_A") (class "Default")
      (node (ref "A_BUS") (pin "5") (pinfunction "5_5") (pintype "passive"))
      (node (ref "GATE31") (pin "A") (pinfunction "A_A") (pintype "input"))
      (node (ref "GATE36") (pin "A") (pinfunction "A_A") (pintype "input"))
      (node (ref "GATE37") (pin "A") (pinfunction "A_A") (pintype "input"))
    )
    (net (code "146") (name "SEC_TENS_B") (class "Default")
      (node (ref "A_BUS") (pin "6") (pinfunction "6_6") (pintype "passive"))
      (node (ref "GATE32") (pin "A") (pinfunction "A_A") (pintype "input"))
      (node (ref "GATE34") (pin "A") (pinfunction "A_A") (pintype "input"))
      (node (ref "GATE37") (pin "B") (pinfunction "B_B") (pintype "input"))
      (node (ref "GATE39") (pin "A") (pinfunction "A_A") (pintype "input"))
    )
    (net (code "147") (name "SEC_TENS_C") (class "Default")
      (node (ref "A_BUS") (pin "7") (pinfunction "7_7") (pintype "passive"))
      (node (ref "GATE33") (pin "A") (pinfunction "A_A") (pintype "input"))
      (node (ref "GATE35") (pin "A") (pinfunction "A_A") (pintype "input"))
      (node (ref "GATE36") (pin "B") (pinfunction "B_B") (pintype "input"))
      (node (ref "GATE38") (pin "A") (pinfunction "A_A") (pintype "input"))
    )
    (net (code "148") (name "SEC_TENS_SEG_AD") (class "Default")
      (node (ref "D_BUS") (pin "8") (pinfunction "8_8") (pintype "passive"))
      (node (ref "GATE41") (pin "Q") (pinfunction "Q_Q") (pintype "output"))
    )
    (net (code "149") (name "SEC_TENS_SEG_B") (class "Default")
      (node (ref "D_BUS") (pin "9") (pinfunction "9_9") (pintype "passive"))
      (node (ref "GATE43") (pin "Q") (pinfunction "Q_Q") (pintype "output"))
    )
    (net (code "150") (name "SEC_TENS_SEG_C") (class "Default")
      (node (ref "D_BUS") (pin "10") (pinfunction "10_10") (pintype "passive"))
      (node (ref "GATE45") (pin "Q") (pinfunction "Q_Q") (pintype "output"))
    )
    (net (code "151") (name "SEC_TENS_SEG_E") (class "Default")
      (node (ref "D_BUS") (pin "11") (pinfunction "11_11") (pintype "passive"))
      (node (ref "GATE36") (pin "Q") (pinfunction "Q_Q") (pintype "output"))
      (node (ref "GATE40") (pin "C") (pinfunction "C_C") (pintype "input"))
    )
    (net (code "152") (name "SEC_TENS_SEG_F") (class "Default")
      (node (ref "D_BUS") (pin "12") (pinfunction "12_12") (pintype "passive"))
      (node (ref "GATE47") (pin "Q") (pinfunction "Q_Q") (pintype "output"))
    )
    (net (code "153") (name "SEC_TENS_SEG_G") (class "Default")
      (node (ref "D_BUS") (pin "13") (pinfunction "13_13") (pintype "passive"))
      (node (ref "GATE49") (pin "Q") (pinfunction "Q_Q") (pintype "output"))
    )
    (net (code "154") (name "SEC_UNIT_A") (class "Default")
      (node (ref "A_BUS") (pin "1") (pinfunction "1_1") (pintype "passive"))
      (node (ref "GATE1") (pin "A") (pinfunction "A_A") (pintype "input"))
      (node (ref "GATE10") (pin "A") (pinfunction "A_A") (pintype "input"))
      (node (ref "GATE12") (pin "A") (pinfunction "A_A") (pintype "input"))
      (node (ref "GATE14") (pin "A") (pinfunction "A_A") (pintype "input"))
      (node (ref "GATE7") (pin "A") (pinfunction "A_A") (pintype "input"))
    )
    (net (code "155") (name "SEC_UNIT_B") (class "Default")
      (node (ref "A_BUS") (pin "2") (pinfunction "2_2") (pintype "passive"))
      (node (ref "GATE11") (pin "A") (pinfunction "A_A") (pintype "input"))
      (node (ref "GATE12") (pin "B") (pinfunction "B_B") (pintype "input"))
      (node (ref "GATE13") (pin "A") (pinfunction "A_A") (pintype "input"))
      (node (ref "GATE16") (pin "A") (pinfunction "A_A") (pintype "input"))
      (node (ref "GATE2") (pin "A") (pinfunction "A_A") (pintype "input"))
      (node (ref "GATE7") (pin "B") (pinfunction "B_B") (pintype "input"))
    )
    (net (code "156") (name "SEC_UNIT_C") (class "Default")
      (node (ref "A_BUS") (pin "3") (pinfunction "3_3") (pintype "passive"))
      (node (ref "GATE11") (pin "B") (pinfunction "B_B") (pintype "input"))
      (node (ref "GATE13") (pin "B") (pinfunction "B_B") (pintype "input"))
      (node (ref "GATE3") (pin "A") (pinfunction "A_A") (pintype "input"))
      (node (ref "GATE7") (pin "C") (pinfunction "C_C") (pintype "input"))
      (node (ref "GATE8") (pin "A") (pinfunction "A_A") (pintype "input"))
    )
    (net (code "157") (name "SEC_UNIT_D") (class "Default")
      (node (ref "A_BUS") (pin "4") (pinfunction "4_4") (pintype "passive"))
      (node (ref "GATE10") (pin "B") (pinfunction "B_B") (pintype "input"))
      (node (ref "GATE15") (pin "A") (pinfunction "A_A") (pintype "input"))
      (node (ref "GATE4") (pin "A") (pinfunction "A_A") (pintype "input"))
      (node (ref "GATE5") (pin "A") (pinfunction "A_A") (pintype "input"))
      (node (ref "GATE8") (pin "B") (pinfunction "B_B") (pintype "input"))
    )
    (net (code "158") (name "SEC_UNIT_SEG_A") (class "Default")
      (node (ref "D_BUS") (pin "1") (pinfunction "1_1") (pintype "passive"))
      (node (ref "GATE18") (pin "Q") (pinfunction "Q_Q") (pintype "output"))
    )
    (net (code "159") (name "SEC_UNIT_SEG_B") (class "Default")
      (node (ref "D_BUS") (pin "2") (pinfunction "2_2") (pintype "passive"))
      (node (ref "GATE20") (pin "Q") (pinfunction "Q_Q") (pintype "output"))
    )
    (net (code "160") (name "SEC_UNIT_SEG_C") (class "Default")
      (node (ref "D_BUS") (pin "3") (pinfunction "3_3") (pintype "passive"))
      (node (ref "GATE22") (pin "Q") (pinfunction "Q_Q") (pintype "output"))
    )
    (net (code "161") (name "SEC_UNIT_SEG_D") (class "Default")
      (node (ref "D_BUS") (pin "4") (pinfunction "4_4") (pintype "passive"))
      (node (ref "GATE24") (pin "Q") (pinfunction "Q_Q") (pintype "output"))
    )
    (net (code "162") (name "SEC_UNIT_SEG_E") (class "Default")
      (node (ref "D_BUS") (pin "5") (pinfunction "5_5") (pintype "passive"))
      (node (ref "GATE26") (pin "Q") (pinfunction "Q_Q") (pintype "output"))
    )
    (net (code "163") (name "SEC_UNIT_SEG_F") (class "Default")
      (node (ref "D_BUS") (pin "6") (pinfunction "6_6") (pintype "passive"))
      (node (ref "GATE28") (pin "Q") (pinfunction "Q_Q") (pintype "output"))
    )
    (net (code "164") (name "SEC_UNIT_SEG_G") (class "Default")
      (node (ref "D_BUS") (pin "7") (pinfunction "7_7") (pintype "passive"))
      (node (ref "GATE30") (pin "Q") (pinfunction "Q_Q") (pintype "output"))
    )
    (net (code "165") (name "VDD") (class "Default")
      (node (ref "A_BUS") (pin "38") (pinfunction "38_38") (pintype "passive"))
      (node (ref "A_BUS") (pin "40") (pinfunction "40_40") (pintype "passive"))
      (node (ref "C1") (pin "+") (pinfunction "+_+") (pintype "passive"))
      (node (ref "R1") (pin "1") (pinfunction "1_1") (pintype "passive"))
    )
    (net (code "166") (name "VSS") (class "Default")
      (node (ref "A_BUS") (pin "37") (pinfunction "37_37") (pintype "passive"))
      (node (ref "A_BUS") (pin "39") (pinfunction "39_39") (pintype "passive"))
      (node (ref "C1") (pin "-") (pinfunction "-_-") (pintype "passive"))
    )
    (net (code "167") (name "unconnected-(A_BUS-Pad21)") (class "Default")
      (node (ref "A_BUS") (pin "21") (pinfunction "21_21") (pintype "passive"))
    )
    (net (code "168") (name "unconnected-(A_BUS-Pad22)") (class "Default")
      (node (ref "A_BUS") (pin "22") (pinfunction "22_22") (pintype "passive"))
    )
    (net (code "169") (name "unconnected-(A_BUS-Pad23)") (class "Default")
      (node (ref "A_BUS") (pin "23") (pinfunction "23_23") (pintype "passive"))
    )
    (net (code "170") (name "unconnected-(A_BUS-Pad24)") (class "Default")
      (node (ref "A_BUS") (pin "24") (pinfunction "24_24") (pintype "passive"))
    )
    (net (code "171") (name "unconnected-(A_BUS-Pad25)") (class "Default")
      (node (ref "A_BUS") (pin "25") (pinfunction "25_25") (pintype "passive"))
    )
    (net (code "172") (name "unconnected-(A_BUS-Pad26)") (class "Default")
      (node (ref "A_BUS") (pin "26") (pinfunction "26_26") (pintype "passive"))
    )
    (net (code "173") (name "unconnected-(A_BUS-Pad27)") (class "Default")
      (node (ref "A_BUS") (pin "27") (pinfunction "27_27") (pintype "passive"))
    )
    (net (code "174") (name "unconnected-(A_BUS-Pad28)") (class "Default")
      (node (ref "A_BUS") (pin "28") (pinfunction "28_28") (pintype "passive"))
    )
    (net (code "175") (name "unconnected-(A_BUS-Pad30)") (class "Default")
      (node (ref "A_BUS") (pin "30") (pinfunction "30_30") (pintype "passive"))
    )
    (net (code "176") (name "unconnected-(A_BUS-Pad36)") (class "Default")
      (node (ref "A_BUS") (pin "36") (pinfunction "36_36") (pintype "passive"))
    )
    (net (code "177") (name "unconnected-(B_BUS-Pad1)") (class "Default")
      (node (ref "B_BUS") (pin "1") (pinfunction "1_1") (pintype "passive"))
    )
    (net (code "178") (name "unconnected-(B_BUS-Pad2)") (class "Default")
      (node (ref "B_BUS") (pin "2") (pinfunction "2_2") (pintype "passive"))
    )
    (net (code "179") (name "unconnected-(B_BUS-Pad3)") (class "Default")
      (node (ref "B_BUS") (pin "3") (pinfunction "3_3") (pintype "passive"))
    )
    (net (code "180") (name "unconnected-(B_BUS-Pad4)") (class "Default")
      (node (ref "B_BUS") (pin "4") (pinfunction "4_4") (pintype "passive"))
    )
    (net (code "181") (name "unconnected-(B_BUS-Pad5)") (class "Default")
      (node (ref "B_BUS") (pin "5") (pinfunction "5_5") (pintype "passive"))
    )
    (net (code "182") (name "unconnected-(B_BUS-Pad6)") (class "Default")
      (node (ref "B_BUS") (pin "6") (pinfunction "6_6") (pintype "passive"))
    )
    (net (code "183") (name "unconnected-(B_BUS-Pad7)") (class "Default")
      (node (ref "B_BUS") (pin "7") (pinfunction "7_7") (pintype "passive"))
    )
    (net (code "184") (name "unconnected-(B_BUS-Pad8)") (class "Default")
      (node (ref "B_BUS") (pin "8") (pinfunction "8_8") (pintype "passive"))
    )
    (net (code "185") (name "unconnected-(B_BUS-Pad9)") (class "Default")
      (node (ref "B_BUS") (pin "9") (pinfunction "9_9") (pintype "passive"))
    )
    (net (code "186") (name "unconnected-(B_BUS-Pad10)") (class "Default")
      (node (ref "B_BUS") (pin "10") (pinfunction "10_10") (pintype "passive"))
    )
    (net (code "187") (name "unconnected-(B_BUS-Pad11)") (class "Default")
      (node (ref "B_BUS") (pin "11") (pinfunction "11_11") (pintype "passive"))
    )
    (net (code "188") (name "unconnected-(B_BUS-Pad12)") (class "Default")
      (node (ref "B_BUS") (pin "12") (pinfunction "12_12") (pintype "passive"))
    )
    (net (code "189") (name "unconnected-(B_BUS-Pad13)") (class "Default")
      (node (ref "B_BUS") (pin "13") (pinfunction "13_13") (pintype "passive"))
    )
    (net (code "190") (name "unconnected-(B_BUS-Pad14)") (class "Default")
      (node (ref "B_BUS") (pin "14") (pinfunction "14_14") (pintype "passive"))
    )
    (net (code "191") (name "unconnected-(B_BUS-Pad15)") (class "Default")
      (node (ref "B_BUS") (pin "15") (pinfunction "15_15") (pintype "passive"))
    )
    (net (code "192") (name "unconnected-(B_BUS-Pad16)") (class "Default")
      (node (ref "B_BUS") (pin "16") (pinfunction "16_16") (pintype "passive"))
    )
    (net (code "193") (name "unconnected-(B_BUS-Pad17)") (class "Default")
      (node (ref "B_BUS") (pin "17") (pinfunction "17_17") (pintype "passive"))
    )
    (net (code "194") (name "unconnected-(B_BUS-Pad18)") (class "Default")
      (node (ref "B_BUS") (pin "18") (pinfunction "18_18") (pintype "passive"))
    )
    (net (code "195") (name "unconnected-(B_BUS-Pad19)") (class "Default")
      (node (ref "B_BUS") (pin "19") (pinfunction "19_19") (pintype "passive"))
    )
    (net (code "196") (name "unconnected-(B_BUS-Pad20)") (class "Default")
      (node (ref "B_BUS") (pin "20") (pinfunction "20_20") (pintype "passive"))
    )
    (net (code "197") (name "unconnected-(B_BUS-Pad21)") (class "Default")
      (node (ref "B_BUS") (pin "21") (pinfunction "21_21") (pintype "passive"))
    )
    (net (code "198") (name "unconnected-(B_BUS-Pad22)") (class "Default")
      (node (ref "B_BUS") (pin "22") (pinfunction "22_22") (pintype "passive"))
    )
    (net (code "199") (name "unconnected-(B_BUS-Pad23)") (class "Default")
      (node (ref "B_BUS") (pin "23") (pinfunction "23_23") (pintype "passive"))
    )
    (net (code "200") (name "unconnected-(B_BUS-Pad24)") (class "Default")
      (node (ref "B_BUS") (pin "24") (pinfunction "24_24") (pintype "passive"))
    )
    (net (code "201") (name "unconnected-(B_BUS-Pad25)") (class "Default")
      (node (ref "B_BUS") (pin "25") (pinfunction "25_25") (pintype "passive"))
    )
    (net (code "202") (name "unconnected-(B_BUS-Pad26)") (class "Default")
      (node (ref "B_BUS") (pin "26") (pinfunction "26_26") (pintype "passive"))
    )
    (net (code "203") (name "unconnected-(B_BUS-Pad27)") (class "Default")
      (node (ref "B_BUS") (pin "27") (pinfunction "27_27") (pintype "passive"))
    )
    (net (code "204") (name "unconnected-(B_BUS-Pad28)") (class "Default")
      (node (ref "B_BUS") (pin "28") (pinfunction "28_28") (pintype "passive"))
    )
    (net (code "205") (name "unconnected-(B_BUS-Pad29)") (class "Default")
      (node (ref "B_BUS") (pin "29") (pinfunction "29_29") (pintype "passive"))
    )
    (net (code "206") (name "unconnected-(B_BUS-Pad30)") (class "Default")
      (node (ref "B_BUS") (pin "30") (pinfunction "30_30") (pintype "passive"))
    )
    (net (code "207") (name "unconnected-(B_BUS-Pad31)") (class "Default")
      (node (ref "B_BUS") (pin "31") (pinfunction "31_31") (pintype "passive"))
    )
    (net (code "208") (name "unconnected-(B_BUS-Pad32)") (class "Default")
      (node (ref "B_BUS") (pin "32") (pinfunction "32_32") (pintype "passive"))
    )
    (net (code "209") (name "unconnected-(B_BUS-Pad33)") (class "Default")
      (node (ref "B_BUS") (pin "33") (pinfunction "33_33") (pintype "passive"))
    )
    (net (code "210") (name "unconnected-(B_BUS-Pad34)") (class "Default")
      (node (ref "B_BUS") (pin "34") (pinfunction "34_34") (pintype "passive"))
    )
    (net (code "211") (name "unconnected-(B_BUS-Pad35)") (class "Default")
      (node (ref "B_BUS") (pin "35") (pinfunction "35_35") (pintype "passive"))
    )
    (net (code "212") (name "unconnected-(B_BUS-Pad36)") (class "Default")
      (node (ref "B_BUS") (pin "36") (pinfunction "36_36") (pintype "passive"))
    )
    (net (code "213") (name "unconnected-(B_BUS-Pad37)") (class "Default")
      (node (ref "B_BUS") (pin "37") (pinfunction "37_37") (pintype "passive"))
    )
    (net (code "214") (name "unconnected-(B_BUS-Pad38)") (class "Default")
      (node (ref "B_BUS") (pin "38") (pinfunction "38_38") (pintype "passive"))
    )
    (net (code "215") (name "unconnected-(B_BUS-Pad39)") (class "Default")
      (node (ref "B_BUS") (pin "39") (pinfunction "39_39") (pintype "passive"))
    )
    (net (code "216") (name "unconnected-(B_BUS-Pad40)") (class "Default")
      (node (ref "B_BUS") (pin "40") (pinfunction "40_40") (pintype "passive"))
    )
    (net (code "217") (name "unconnected-(C_BUS-Pad1)") (class "Default")
      (node (ref "C_BUS") (pin "1") (pinfunction "1_1") (pintype "passive"))
    )
    (net (code "218") (name "unconnected-(C_BUS-Pad2)") (class "Default")
      (node (ref "C_BUS") (pin "2") (pinfunction "2_2") (pintype "passive"))
    )
    (net (code "219") (name "unconnected-(C_BUS-Pad3)") (class "Default")
      (node (ref "C_BUS") (pin "3") (pinfunction "3_3") (pintype "passive"))
    )
    (net (code "220") (name "unconnected-(C_BUS-Pad4)") (class "Default")
      (node (ref "C_BUS") (pin "4") (pinfunction "4_4") (pintype "passive"))
    )
    (net (code "221") (name "unconnected-(C_BUS-Pad5)") (class "Default")
      (node (ref "C_BUS") (pin "5") (pinfunction "5_5") (pintype "passive"))
    )
    (net (code "222") (name "unconnected-(C_BUS-Pad6)") (class "Default")
      (node (ref "C_BUS") (pin "6") (pinfunction "6_6") (pintype "passive"))
    )
    (net (code "223") (name "unconnected-(C_BUS-Pad7)") (class "Default")
      (node (ref "C_BUS") (pin "7") (pinfunction "7_7") (pintype "passive"))
    )
    (net (code "224") (name "unconnected-(C_BUS-Pad8)") (class "Default")
      (node (ref "C_BUS") (pin "8") (pinfunction "8_8") (pintype "passive"))
    )
    (net (code "225") (name "unconnected-(C_BUS-Pad9)") (class "Default")
      (node (ref "C_BUS") (pin "9") (pinfunction "9_9") (pintype "passive"))
    )
    (net (code "226") (name "unconnected-(C_BUS-Pad10)") (class "Default")
      (node (ref "C_BUS") (pin "10") (pinfunction "10_10") (pintype "passive"))
    )
    (net (code "227") (name "unconnected-(C_BUS-Pad11)") (class "Default")
      (node (ref "C_BUS") (pin "11") (pinfunction "11_11") (pintype "passive"))
    )
    (net (code "228") (name "unconnected-(C_BUS-Pad12)") (class "Default")
      (node (ref "C_BUS") (pin "12") (pinfunction "12_12") (pintype "passive"))
    )
    (net (code "229") (name "unconnected-(C_BUS-Pad13)") (class "Default")
      (node (ref "C_BUS") (pin "13") (pinfunction "13_13") (pintype "passive"))
    )
    (net (code "230") (name "unconnected-(C_BUS-Pad14)") (class "Default")
      (node (ref "C_BUS") (pin "14") (pinfunction "14_14") (pintype "passive"))
    )
    (net (code "231") (name "unconnected-(C_BUS-Pad15)") (class "Default")
      (node (ref "C_BUS") (pin "15") (pinfunction "15_15") (pintype "passive"))
    )
    (net (code "232") (name "unconnected-(C_BUS-Pad16)") (class "Default")
      (node (ref "C_BUS") (pin "16") (pinfunction "16_16") (pintype "passive"))
    )
    (net (code "233") (name "unconnected-(C_BUS-Pad17)") (class "Default")
      (node (ref "C_BUS") (pin "17") (pinfunction "17_17") (pintype "passive"))
    )
    (net (code "234") (name "unconnected-(C_BUS-Pad18)") (class "Default")
      (node (ref "C_BUS") (pin "18") (pinfunction "18_18") (pintype "passive"))
    )
    (net (code "235") (name "unconnected-(C_BUS-Pad19)") (class "Default")
      (node (ref "C_BUS") (pin "19") (pinfunction "19_19") (pintype "passive"))
    )
    (net (code "236") (name "unconnected-(C_BUS-Pad20)") (class "Default")
      (node (ref "C_BUS") (pin "20") (pinfunction "20_20") (pintype "passive"))
    )
    (net (code "237") (name "unconnected-(C_BUS-Pad21)") (class "Default")
      (node (ref "C_BUS") (pin "21") (pinfunction "21_21") (pintype "passive"))
    )
    (net (code "238") (name "unconnected-(C_BUS-Pad22)") (class "Default")
      (node (ref "C_BUS") (pin "22") (pinfunction "22_22") (pintype "passive"))
    )
    (net (code "239") (name "unconnected-(C_BUS-Pad23)") (class "Default")
      (node (ref "C_BUS") (pin "23") (pinfunction "23_23") (pintype "passive"))
    )
    (net (code "240") (name "unconnected-(C_BUS-Pad24)") (class "Default")
      (node (ref "C_BUS") (pin "24") (pinfunction "24_24") (pintype "passive"))
    )
    (net (code "241") (name "unconnected-(C_BUS-Pad25)") (class "Default")
      (node (ref "C_BUS") (pin "25") (pinfunction "25_25") (pintype "passive"))
    )
    (net (code "242") (name "unconnected-(C_BUS-Pad26)") (class "Default")
      (node (ref "C_BUS") (pin "26") (pinfunction "26_26") (pintype "passive"))
    )
    (net (code "243") (name "unconnected-(C_BUS-Pad27)") (class "Default")
      (node (ref "C_BUS") (pin "27") (pinfunction "27_27") (pintype "passive"))
    )
    (net (code "244") (name "unconnected-(C_BUS-Pad28)") (class "Default")
      (node (ref "C_BUS") (pin "28") (pinfunction "28_28") (pintype "passive"))
    )
    (net (code "245") (name "unconnected-(C_BUS-Pad29)") (class "Default")
      (node (ref "C_BUS") (pin "29") (pinfunction "29_29") (pintype "passive"))
    )
    (net (code "246") (name "unconnected-(C_BUS-Pad30)") (class "Default")
      (node (ref "C_BUS") (pin "30") (pinfunction "30_30") (pintype "passive"))
    )
    (net (code "247") (name "unconnected-(C_BUS-Pad31)") (class "Default")
      (node (ref "C_BUS") (pin "31") (pinfunction "31_31") (pintype "passive"))
    )
    (net (code "248") (name "unconnected-(C_BUS-Pad32)") (class "Default")
      (node (ref "C_BUS") (pin "32") (pinfunction "32_32") (pintype "passive"))
    )
    (net (code "249") (name "unconnected-(C_BUS-Pad33)") (class "Default")
      (node (ref "C_BUS") (pin "33") (pinfunction "33_33") (pintype "passive"))
    )
    (net (code "250") (name "unconnected-(C_BUS-Pad34)") (class "Default")
      (node (ref "C_BUS") (pin "34") (pinfunction "34_34") (pintype "passive"))
    )
    (net (code "251") (name "unconnected-(C_BUS-Pad35)") (class "Default")
      (node (ref "C_BUS") (pin "35") (pinfunction "35_35") (pintype "passive"))
    )
    (net (code "252") (name "unconnected-(C_BUS-Pad36)") (class "Default")
      (node (ref "C_BUS") (pin "36") (pinfunction "36_36") (pintype "passive"))
    )
    (net (code "253") (name "unconnected-(C_BUS-Pad37)") (class "Default")
      (node (ref "C_BUS") (pin "37") (pinfunction "37_37") (pintype "passive"))
    )
    (net (code "254") (name "unconnected-(C_BUS-Pad38)") (class "Default")
      (node (ref "C_BUS") (pin "38") (pinfunction "38_38") (pintype "passive"))
    )
    (net (code "255") (name "unconnected-(C_BUS-Pad39)") (class "Default")
      (node (ref "C_BUS") (pin "39") (pinfunction "39_39") (pintype "passive"))
    )
    (net (code "256") (name "unconnected-(C_BUS-Pad40)") (class "Default")
      (node (ref "C_BUS") (pin "40") (pinfunction "40_40") (pintype "passive"))
    )
    (net (code "257") (name "unconnected-(D_BUS-Pad40)") (class "Default")
      (node (ref "D_BUS") (pin "40") (pinfunction "40_40") (pintype "passive"))
    )
  )
)
